# BMS_Master.net
KiCad netlist of a schematic drawn in EAGLE
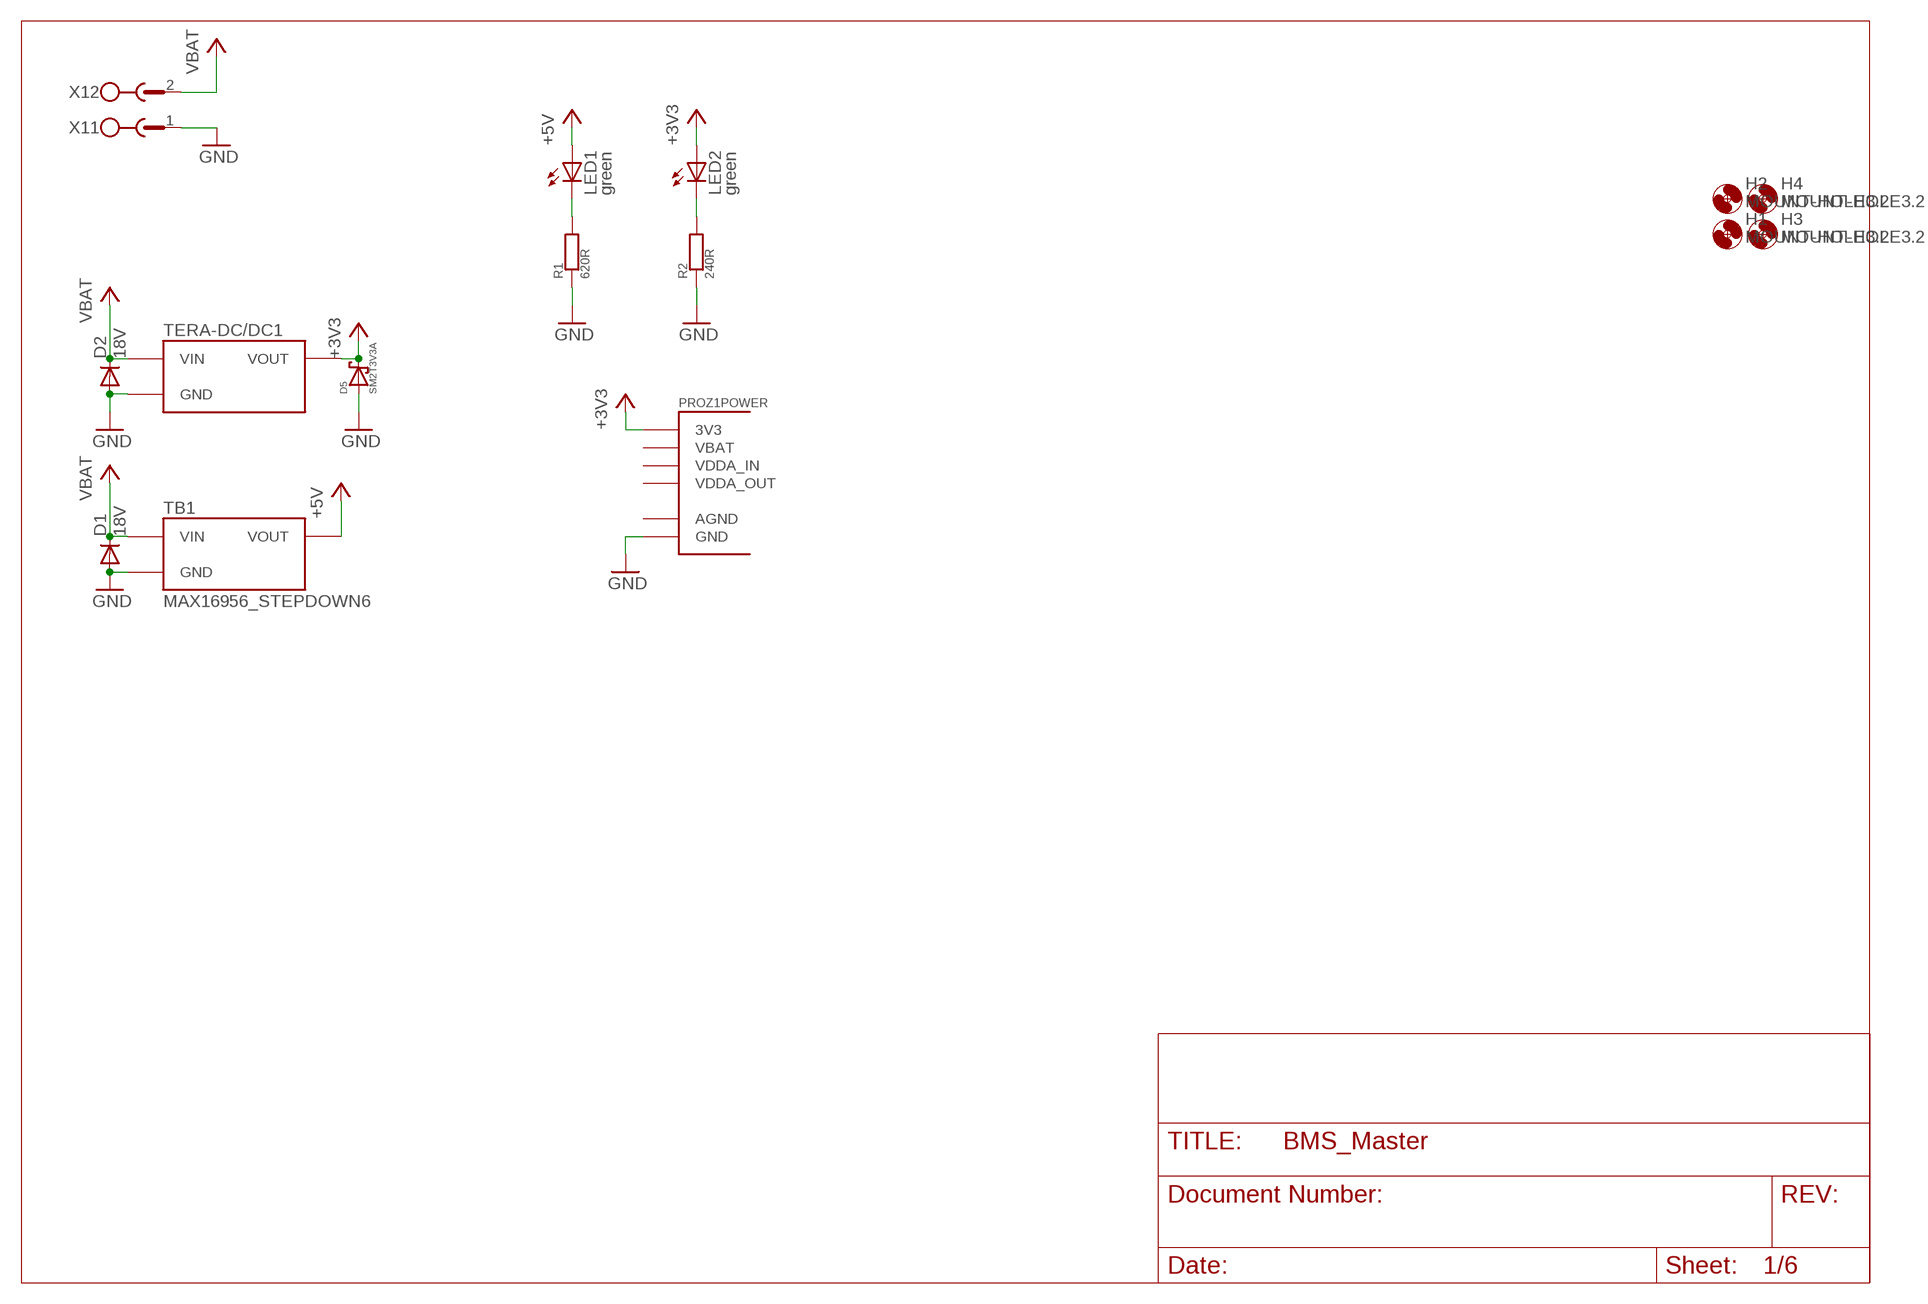
[diagram p0: schematic, sheet 1]
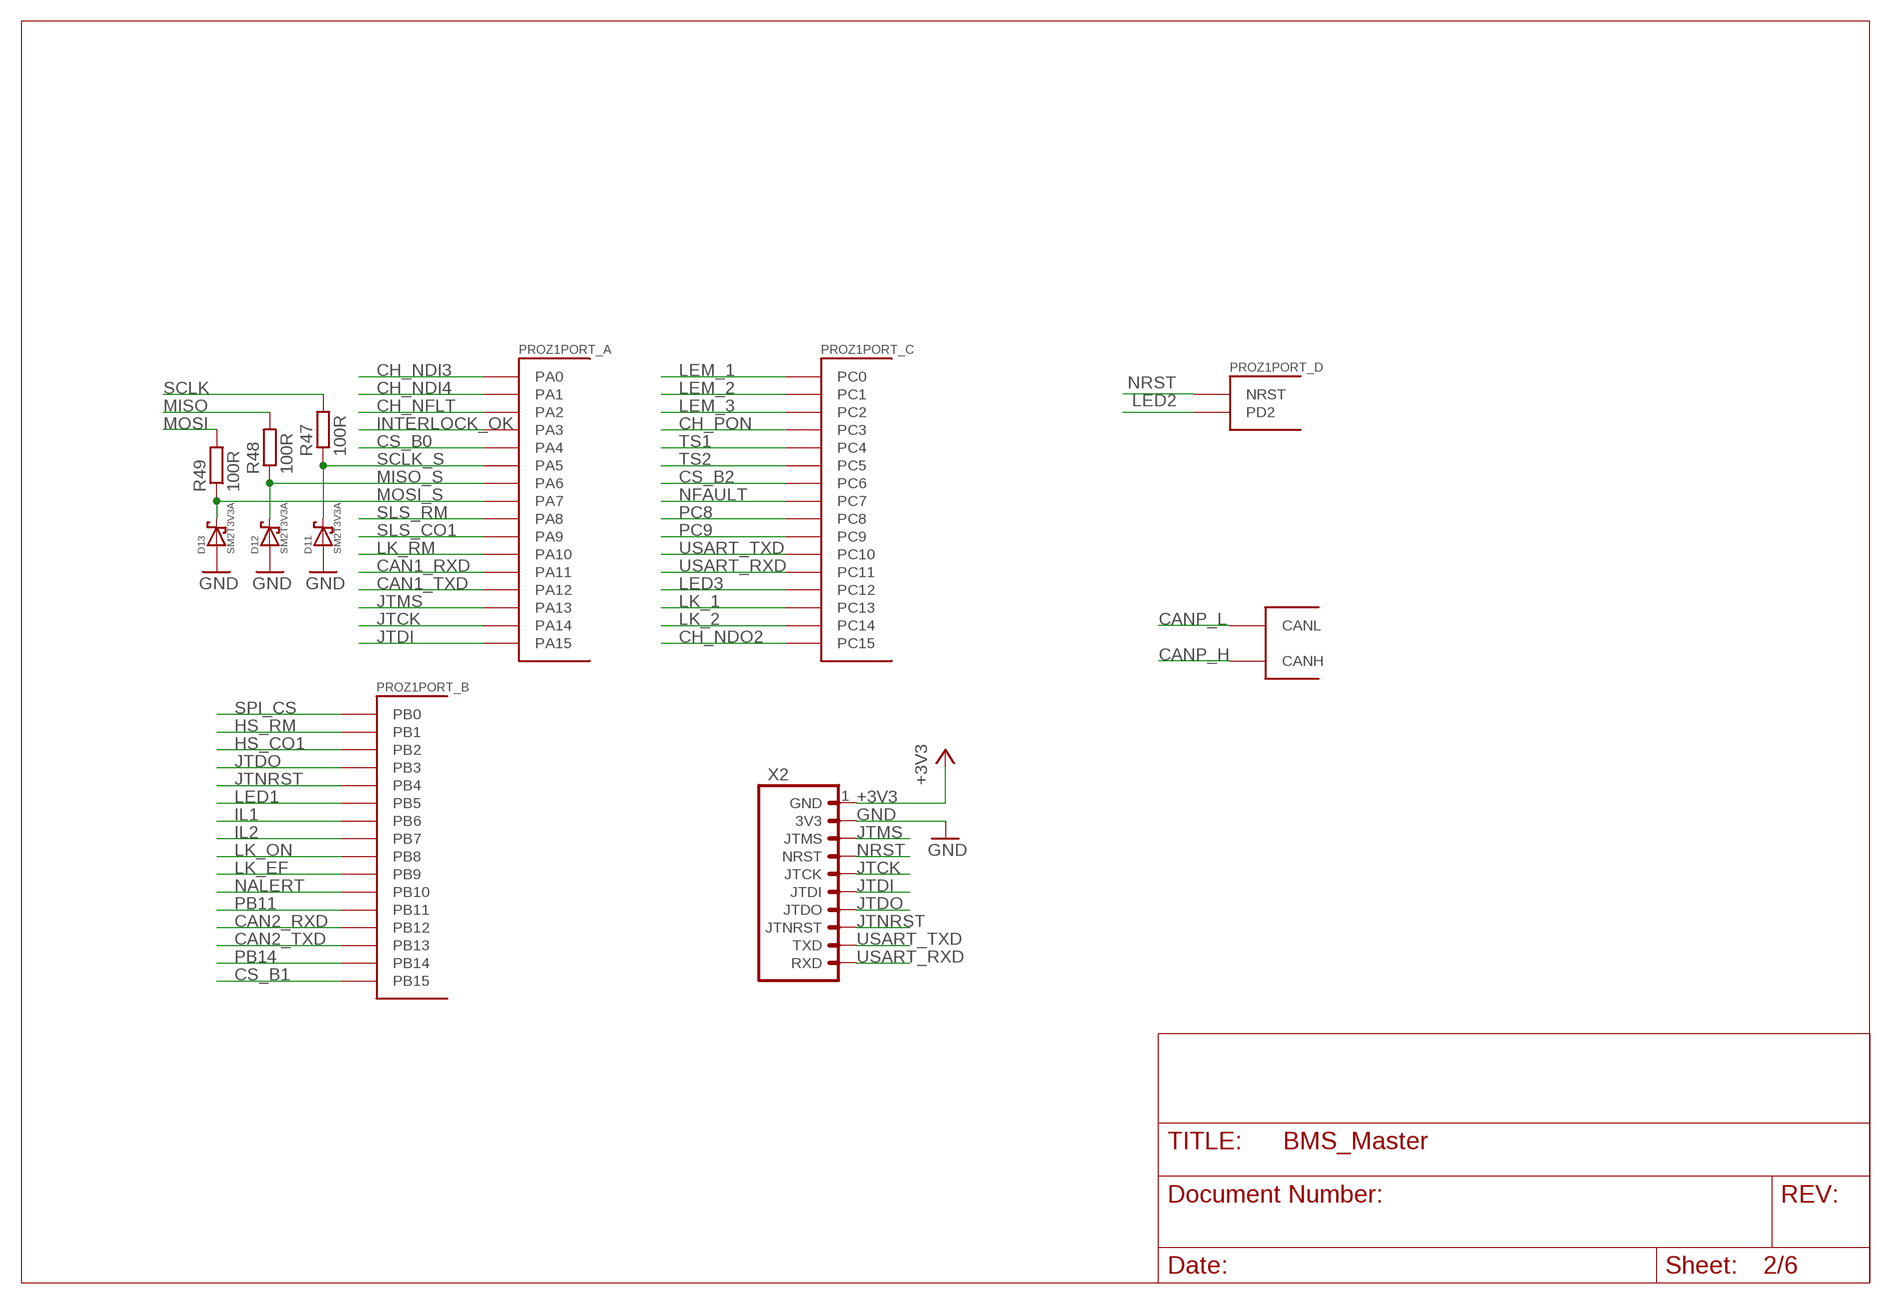
[diagram p1: schematic, sheet 2]
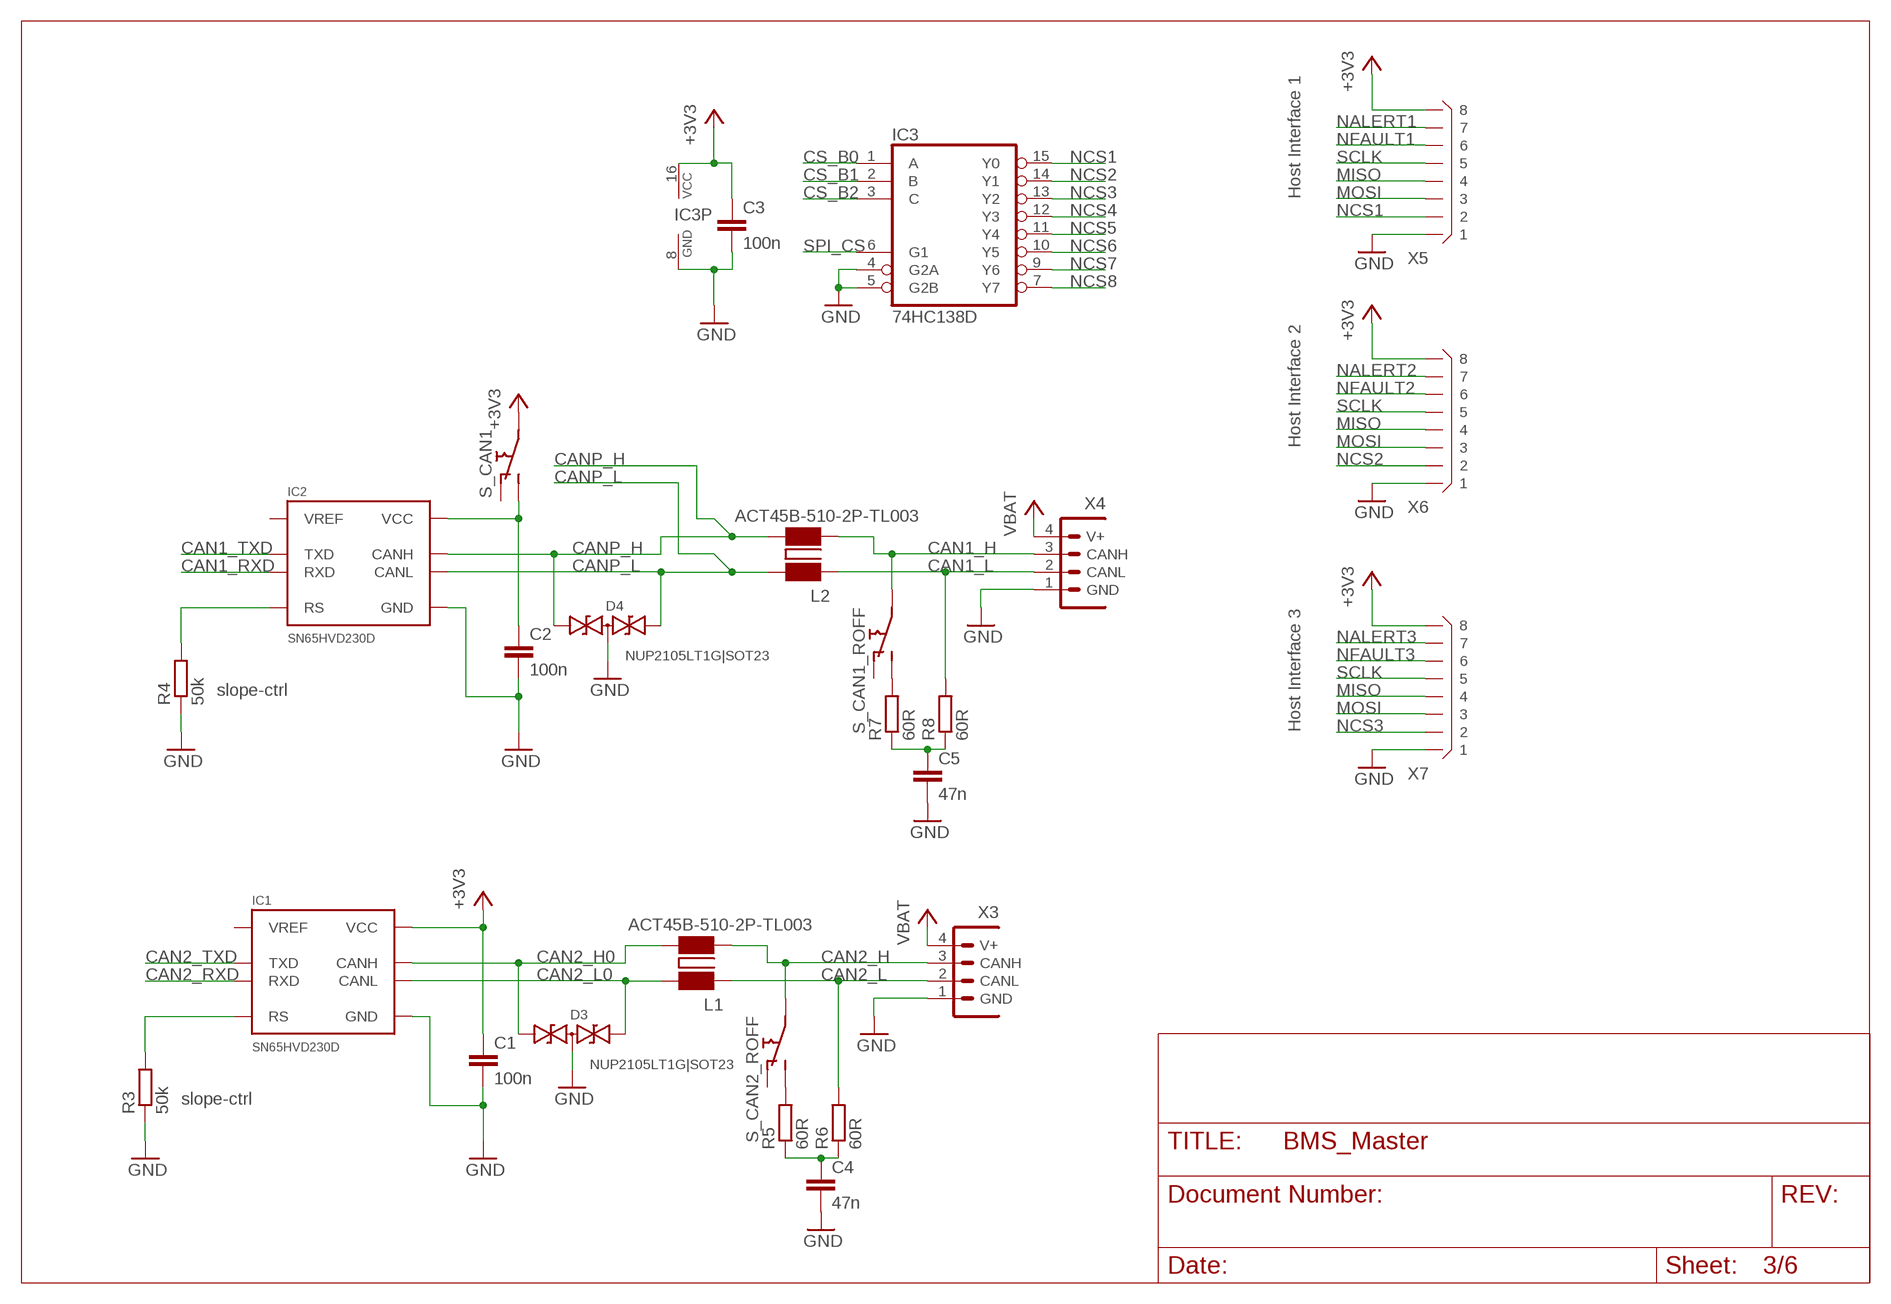
[diagram p2: schematic, sheet 3]
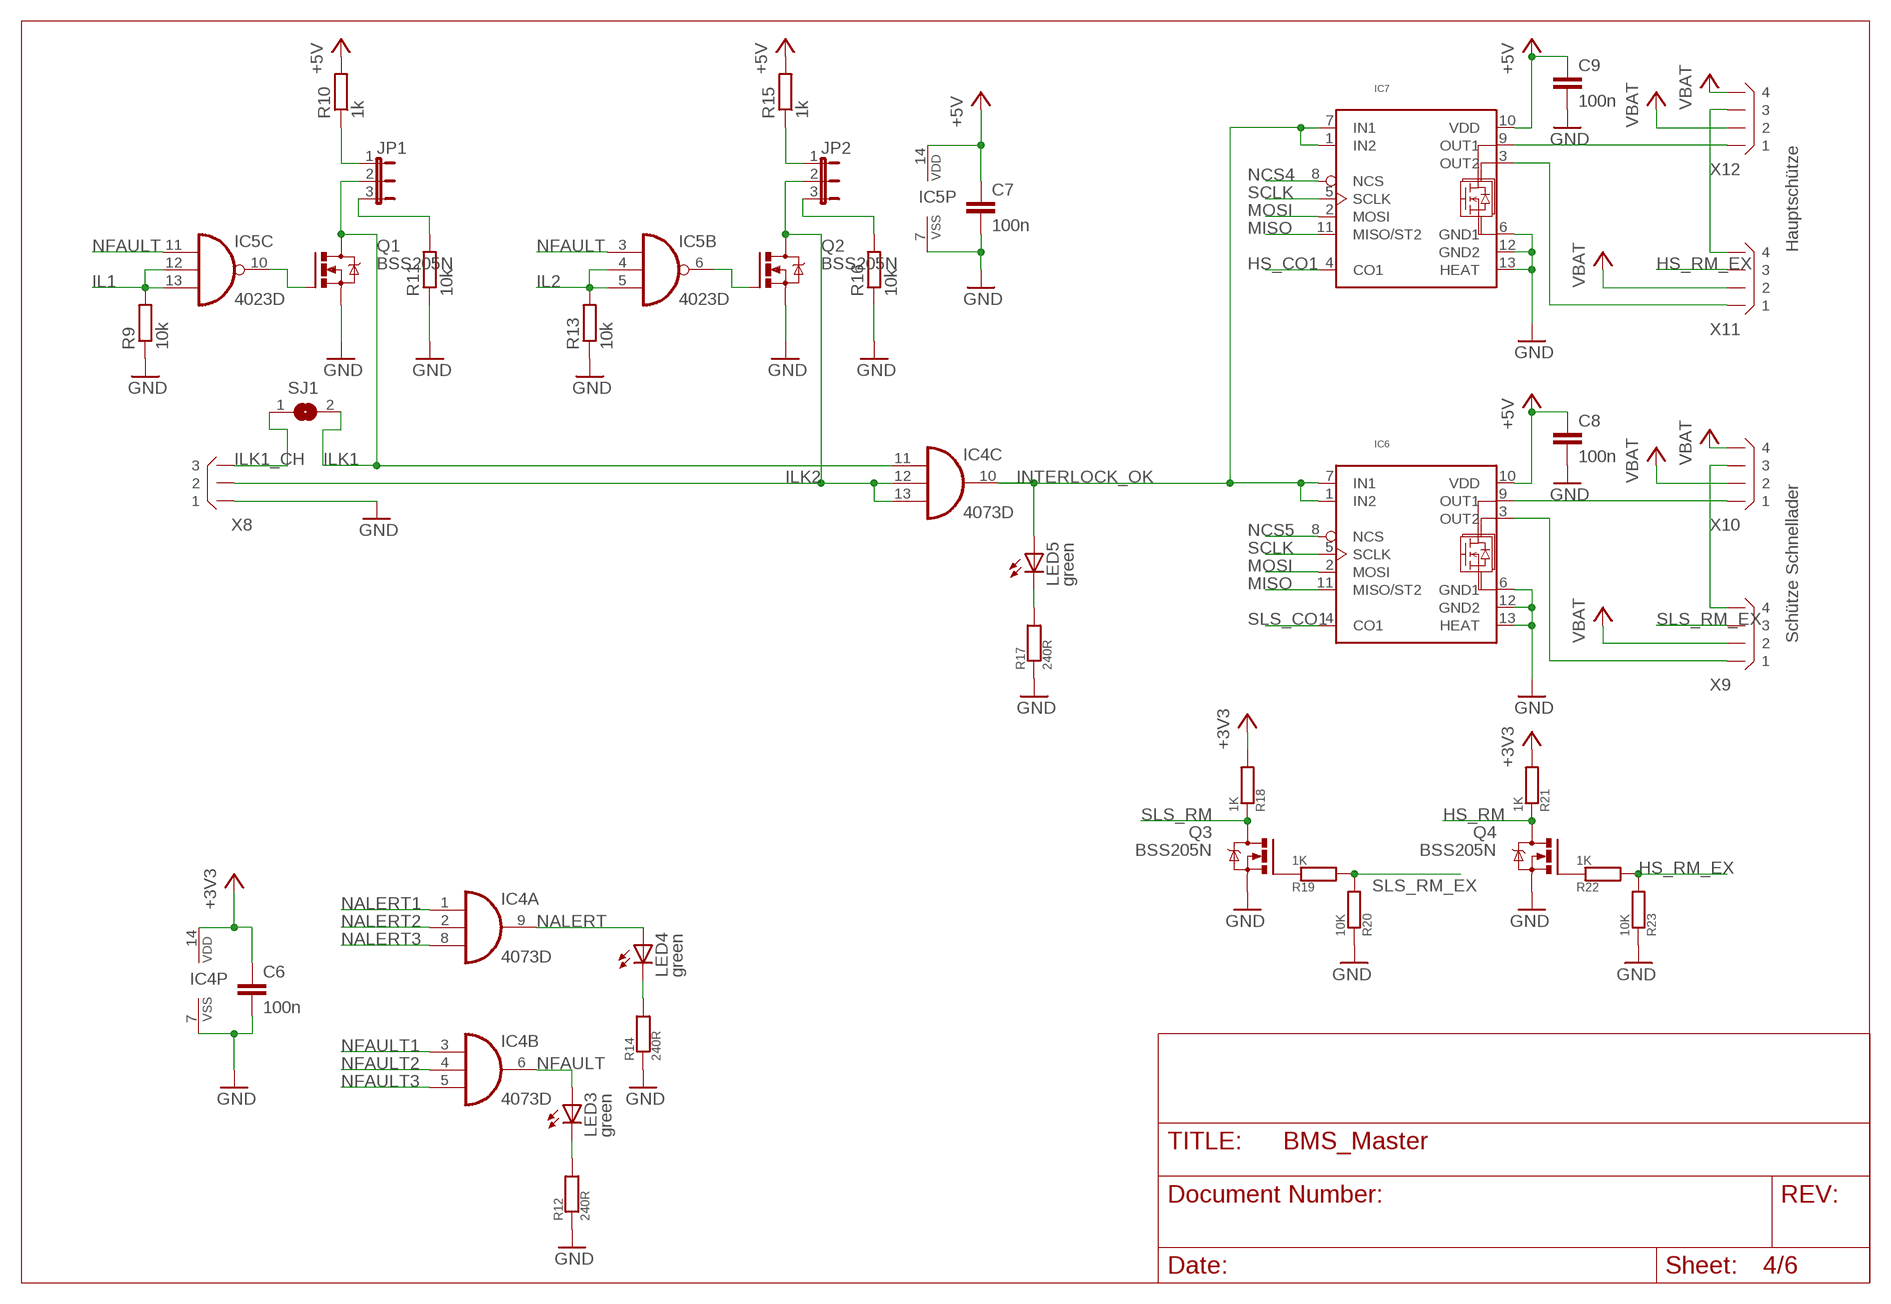
[diagram p3: schematic, sheet 4]
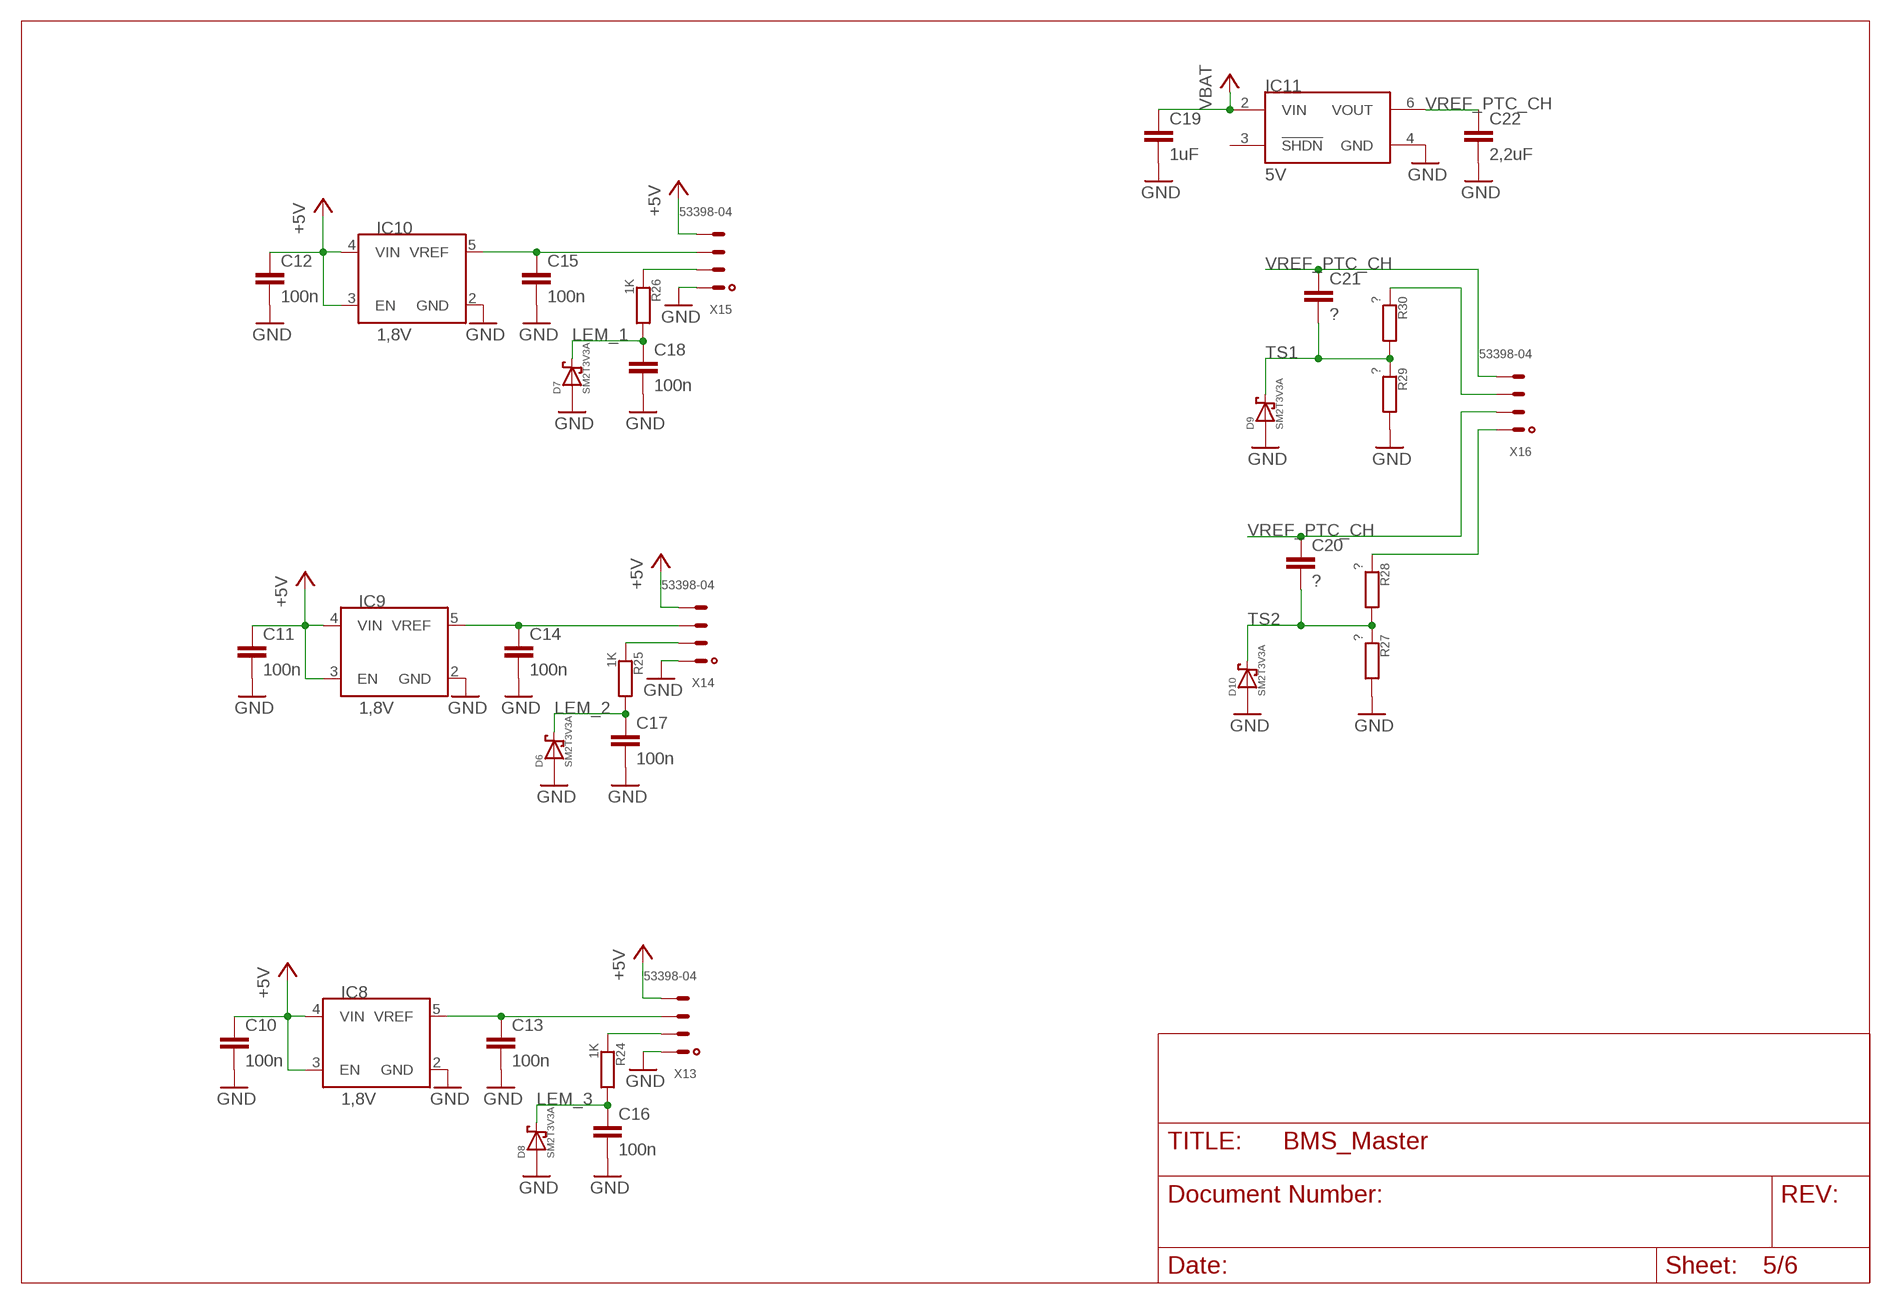
[diagram p4: schematic, sheet 5]
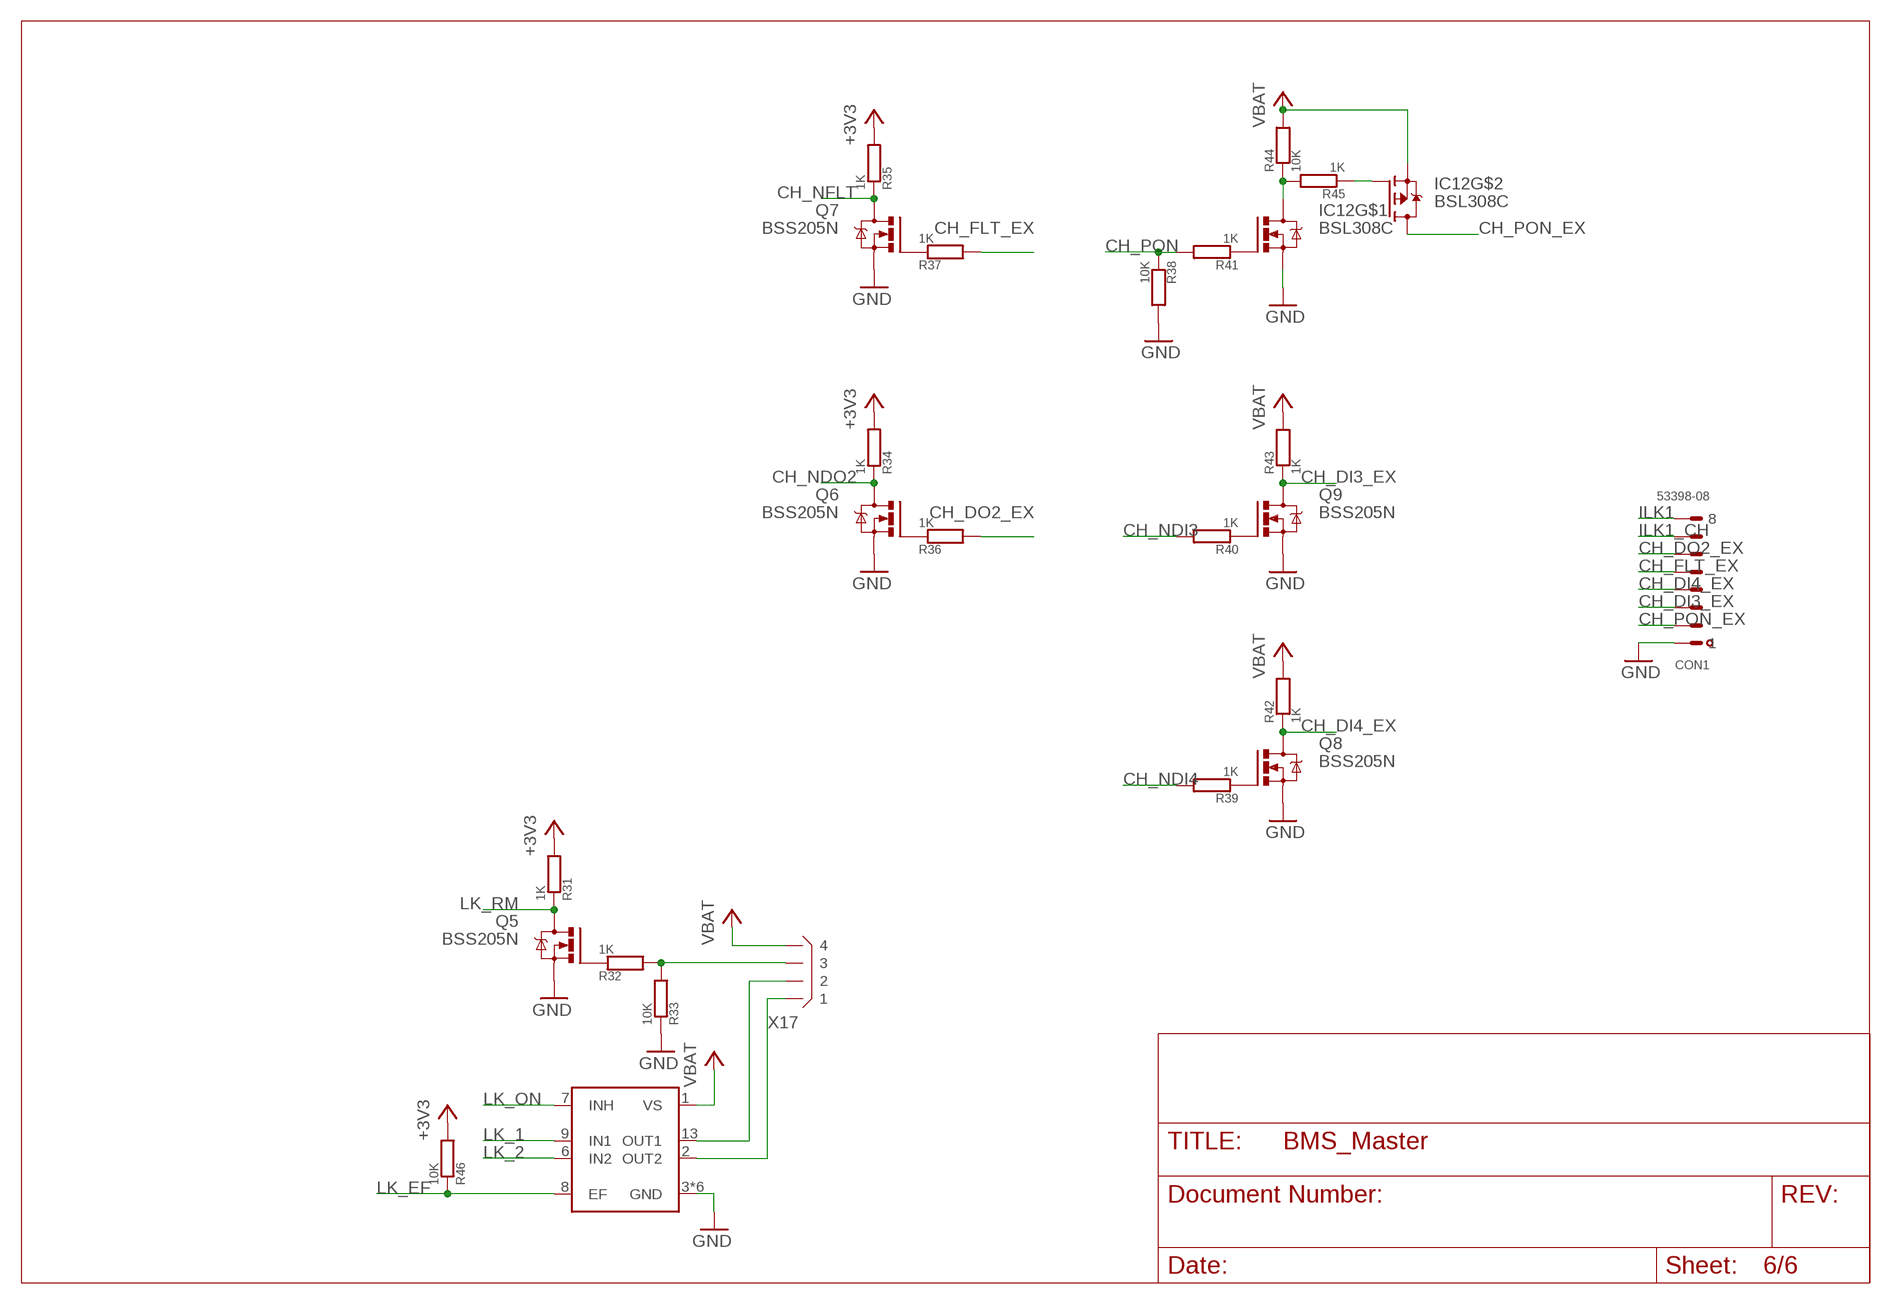
[diagram p5: schematic, sheet 6]

(export (version "E")
  (design (tool "Eeschema 10.0.6"))
  (components
    (comp (ref "C1")
      (value "100n")
      (footprint "eagle-import:C0805")
      (libsource (lib "eagle-import") (part "C-EUC0805"))
    )
    (comp (ref "C2")
      (value "100n")
      (footprint "eagle-import:C0805")
      (libsource (lib "eagle-import") (part "C-EUC0805"))
    )
    (comp (ref "C3")
      (value "100n")
      (footprint "eagle-import:C0805")
      (libsource (lib "eagle-import") (part "C-EUC0805"))
    )
    (comp (ref "C4")
      (value "47n")
      (footprint "eagle-import:C0805")
      (libsource (lib "eagle-import") (part "C-EUC0805"))
    )
    (comp (ref "C5")
      (value "47n")
      (footprint "eagle-import:C0805")
      (libsource (lib "eagle-import") (part "C-EUC0805"))
    )
    (comp (ref "D3")
      (value "NUP2105LT1G|SOT23")
      (footprint "eagle-import:SOT23")
      (libsource (lib "eagle-import") (part "NUP2105LT1G|SOT23"))
    )
    (comp (ref "D4")
      (value "NUP2105LT1G|SOT23")
      (footprint "eagle-import:SOT23")
      (libsource (lib "eagle-import") (part "NUP2105LT1G|SOT23"))
    )
    (comp (ref "IC1")
      (value "SN65HVD230D")
      (footprint "eagle-import:SO08")
      (libsource (lib "eagle-import") (part "SN65HVD23D0"))
    )
    (comp (ref "IC2")
      (value "SN65HVD230D")
      (footprint "eagle-import:SO08")
      (libsource (lib "eagle-import") (part "SN65HVD23D0"))
    )
    (comp (ref "IC3")
      (value "74HC138D")
      (footprint "eagle-import:SO16")
      (libsource (lib "eagle-import") (part "74138DHC"))
    )
    (comp (ref "L1")
      (value "ACT45B-510-2P-TL003")
      (footprint "eagle-import:ACT45B")
      (libsource (lib "eagle-import") (part "ACT45B-510-2P-TL003"))
    )
    (comp (ref "L2")
      (value "ACT45B-510-2P-TL003")
      (footprint "eagle-import:ACT45B")
      (libsource (lib "eagle-import") (part "ACT45B-510-2P-TL003"))
    )
    (comp (ref "R3")
      (value "50k")
      (footprint "eagle-import:R0805")
      (libsource (lib "eagle-import") (part "R-EU_R0805"))
    )
    (comp (ref "R4")
      (value "50k")
      (footprint "eagle-import:R0805")
      (libsource (lib "eagle-import") (part "R-EU_R0805"))
    )
    (comp (ref "R5")
      (value "60R")
      (footprint "eagle-import:R0805")
      (libsource (lib "eagle-import") (part "R-EU_R0805"))
    )
    (comp (ref "R6")
      (value "60R")
      (footprint "eagle-import:R0805")
      (libsource (lib "eagle-import") (part "R-EU_R0805"))
    )
    (comp (ref "R7")
      (value "60R")
      (footprint "eagle-import:R0805")
      (libsource (lib "eagle-import") (part "R-EU_R0805"))
    )
    (comp (ref "R8")
      (value "60R")
      (footprint "eagle-import:R0805")
      (libsource (lib "eagle-import") (part "R-EU_R0805"))
    )
    (comp (ref "S_CAN1")
      (value "JUMPER_ORS")
      (footprint "eagle-import:J_OR_S")
      (libsource (lib "eagle-import") (part "JUMPER_ORS"))
    )
    (comp (ref "S_CAN1_ROFF")
      (value "JUMPER_ORS")
      (footprint "eagle-import:J_OR_S")
      (libsource (lib "eagle-import") (part "JUMPER_ORS"))
    )
    (comp (ref "S_CAN2_ROFF")
      (value "JUMPER_ORS")
      (footprint "eagle-import:J_OR_S")
      (libsource (lib "eagle-import") (part "JUMPER_ORS"))
    )
    (comp (ref "X3")
      (value "CIOC_4-1-FV-A_CAN-BELEGUNG")
      (footprint "eagle-import:CIOC_4-1-FV")
      (libsource (lib "eagle-import") (part "CIOC_4-1-FV-A_CAN-BELEGUNG"))
    )
    (comp (ref "X4")
      (value "CIOC_4-1-FV-A_CAN-BELEGUNG")
      (footprint "eagle-import:CIOC_4-1-FV")
      (libsource (lib "eagle-import") (part "CIOC_4-1-FV-A_CAN-BELEGUNG"))
    )
    (comp (ref "X5")
      (value "B8B-XH")
      (footprint "eagle-import:B8B-XH")
      (libsource (lib "eagle-import") (part "?8B-XHB"))
    )
    (comp (ref "X6")
      (value "B8B-XH")
      (footprint "eagle-import:B8B-XH")
      (libsource (lib "eagle-import") (part "?8B-XHB"))
    )
    (comp (ref "X7")
      (value "B8B-XH")
      (footprint "eagle-import:B8B-XH")
      (libsource (lib "eagle-import") (part "?8B-XHB"))
    )
    (comp (ref "C10")
      (value "100n")
      (footprint "eagle-import:C0805")
      (libsource (lib "eagle-import") (part "C-EUC0805"))
    )
    (comp (ref "C11")
      (value "100n")
      (footprint "eagle-import:C0805")
      (libsource (lib "eagle-import") (part "C-EUC0805"))
    )
    (comp (ref "C12")
      (value "100n")
      (footprint "eagle-import:C0805")
      (libsource (lib "eagle-import") (part "C-EUC0805"))
    )
    (comp (ref "C13")
      (value "100n")
      (footprint "eagle-import:C0805")
      (libsource (lib "eagle-import") (part "C-EUC0805"))
    )
    (comp (ref "C14")
      (value "100n")
      (footprint "eagle-import:C0805")
      (libsource (lib "eagle-import") (part "C-EUC0805"))
    )
    (comp (ref "C15")
      (value "100n")
      (footprint "eagle-import:C0805")
      (libsource (lib "eagle-import") (part "C-EUC0805"))
    )
    (comp (ref "C16")
      (value "100n")
      (footprint "eagle-import:C0805")
      (libsource (lib "eagle-import") (part "C-EUC0805"))
    )
    (comp (ref "C17")
      (value "100n")
      (footprint "eagle-import:C0805")
      (libsource (lib "eagle-import") (part "C-EUC0805"))
    )
    (comp (ref "C18")
      (value "100n")
      (footprint "eagle-import:C0805")
      (libsource (lib "eagle-import") (part "C-EUC0805"))
    )
    (comp (ref "C19")
      (value "1uF")
      (footprint "eagle-import:C0805")
      (libsource (lib "eagle-import") (part "C-EUC0805"))
    )
    (comp (ref "C20")
      (value "?")
      (footprint "eagle-import:C0805")
      (libsource (lib "eagle-import") (part "C-EUC0805"))
    )
    (comp (ref "C21")
      (value "?")
      (footprint "eagle-import:C0805")
      (libsource (lib "eagle-import") (part "C-EUC0805"))
    )
    (comp (ref "C22")
      (value "2,2uF")
      (footprint "eagle-import:C0805")
      (libsource (lib "eagle-import") (part "C-EUC0805"))
    )
    (comp (ref "D6")
      (value "SM2T3V3A")
      (footprint "eagle-import:SM2T3V3A")
      (libsource (lib "eagle-import") (part "SM2T3V3A"))
    )
    (comp (ref "D7")
      (value "SM2T3V3A")
      (footprint "eagle-import:SM2T3V3A")
      (libsource (lib "eagle-import") (part "SM2T3V3A"))
    )
    (comp (ref "D8")
      (value "SM2T3V3A")
      (footprint "eagle-import:SM2T3V3A")
      (libsource (lib "eagle-import") (part "SM2T3V3A"))
    )
    (comp (ref "D9")
      (value "SM2T3V3A")
      (footprint "eagle-import:SM2T3V3A")
      (libsource (lib "eagle-import") (part "SM2T3V3A"))
    )
    (comp (ref "D10")
      (value "SM2T3V3A")
      (footprint "eagle-import:SM2T3V3A")
      (libsource (lib "eagle-import") (part "SM2T3V3A"))
    )
    (comp (ref "IC8")
      (value "1,8V")
      (footprint "eagle-import:SOT23-5L")
      (libsource (lib "eagle-import") (part "LM4132L"))
    )
    (comp (ref "IC9")
      (value "1,8V")
      (footprint "eagle-import:SOT23-5L")
      (libsource (lib "eagle-import") (part "LM4132L"))
    )
    (comp (ref "IC10")
      (value "1,8V")
      (footprint "eagle-import:SOT23-5L")
      (libsource (lib "eagle-import") (part "LM4132L"))
    )
    (comp (ref "IC11")
      (value "5V")
      (footprint "eagle-import:SO08")
      (libsource (lib "eagle-import") (part "LT1461"))
    )
    (comp (ref "R24")
      (value "1K")
      (footprint "eagle-import:R0805")
      (libsource (lib "eagle-import") (part "R"))
    )
    (comp (ref "R25")
      (value "1K")
      (footprint "eagle-import:R0805")
      (libsource (lib "eagle-import") (part "R"))
    )
    (comp (ref "R26")
      (value "1K")
      (footprint "eagle-import:R0805")
      (libsource (lib "eagle-import") (part "R"))
    )
    (comp (ref "R27")
      (value "?")
      (footprint "eagle-import:R0805")
      (libsource (lib "eagle-import") (part "R"))
    )
    (comp (ref "R28")
      (value "?")
      (footprint "eagle-import:R0805")
      (libsource (lib "eagle-import") (part "R"))
    )
    (comp (ref "R29")
      (value "?")
      (footprint "eagle-import:R0805")
      (libsource (lib "eagle-import") (part "R"))
    )
    (comp (ref "R30")
      (value "?")
      (footprint "eagle-import:R0805")
      (libsource (lib "eagle-import") (part "R"))
    )
    (comp (ref "X13")
      (value "53398-04")
      (footprint "eagle-import:53398-04")
      (libsource (lib "eagle-import") (part "53?-04398"))
    )
    (comp (ref "X14")
      (value "53398-04")
      (footprint "eagle-import:53398-04")
      (libsource (lib "eagle-import") (part "53?-04398"))
    )
    (comp (ref "X15")
      (value "53398-04")
      (footprint "eagle-import:53398-04")
      (libsource (lib "eagle-import") (part "53?-04398"))
    )
    (comp (ref "X16")
      (value "53398-04")
      (footprint "eagle-import:53398-04")
      (libsource (lib "eagle-import") (part "53?-04398"))
    )
    (comp (ref "D1")
      (value "18V")
      (footprint "eagle-import:DO214AA")
      (libsource (lib "eagle-import") (part "DIODE-DO214AA"))
    )
    (comp (ref "D2")
      (value "18V")
      (footprint "eagle-import:DO214AA")
      (libsource (lib "eagle-import") (part "DIODE-DO214AA"))
    )
    (comp (ref "D5")
      (value "SM2T3V3A")
      (footprint "eagle-import:SM2T3V3A")
      (libsource (lib "eagle-import") (part "SM2T3V3A"))
    )
    (comp (ref "H1")
      (value "MOUNT-HOLE3.2")
      (footprint "eagle-import:3,2")
      (libsource (lib "eagle-import") (part "MOUNT-HOLE3.2"))
    )
    (comp (ref "H2")
      (value "MOUNT-HOLE3.2")
      (footprint "eagle-import:3,2")
      (libsource (lib "eagle-import") (part "MOUNT-HOLE3.2"))
    )
    (comp (ref "H3")
      (value "MOUNT-HOLE3.2")
      (footprint "eagle-import:3,2")
      (libsource (lib "eagle-import") (part "MOUNT-HOLE3.2"))
    )
    (comp (ref "H4")
      (value "MOUNT-HOLE3.2")
      (footprint "eagle-import:3,2")
      (libsource (lib "eagle-import") (part "MOUNT-HOLE3.2"))
    )
    (comp (ref "LED1")
      (value "green")
      (footprint "eagle-import:CHIP-LED0805")
      (libsource (lib "eagle-import") (part "LEDCHIP-LED0805"))
    )
    (comp (ref "LED2")
      (value "green")
      (footprint "eagle-import:CHIP-LED0805")
      (libsource (lib "eagle-import") (part "LEDCHIP-LED0805"))
    )
    (comp (ref "PROZ1")
      (value "STM32F4_PROZESSORBOARDRPZ")
      (footprint "eagle-import:STM32F4_PROZESSORBOARD")
      (libsource (lib "eagle-import") (part "STM32F4_PROZESSORBOARDRPZ"))
    )
    (comp (ref "R1")
      (value "620R")
      (footprint "eagle-import:R0805")
      (libsource (lib "eagle-import") (part "R"))
    )
    (comp (ref "R2")
      (value "240R")
      (footprint "eagle-import:R0805")
      (libsource (lib "eagle-import") (part "R"))
    )
    (comp (ref "TB1")
      (value "MAX16956_STEPDOWN6")
      (footprint "eagle-import:MAX16956_STEPDOWN6")
      (libsource (lib "eagle-import") (part "MAX16956_STEPDOWN6"))
    )
    (comp (ref "TERA-DC/DC1")
      (value "MAX5035_STEPDOWN3")
      (footprint "eagle-import:MAX5035_STEPDOWN3")
      (libsource (lib "eagle-import") (part "MAX5035_STEPDOWN3"))
    )
    (comp (ref "X1")
      (value "MSTBX2MSTBV2_GF")
      (footprint "eagle-import:MSTBV2_GF")
      (libsource (lib "eagle-import") (part "MSTBX2MSTBV2_GF"))
    )
    (comp (ref "CON1")
      (value "53398-08")
      (footprint "eagle-import:53398-08")
      (libsource (lib "eagle-import") (part "53?-08398"))
    )
    (comp (ref "IC12")
      (value "BSL308C")
      (footprint "eagle-import:TSOP-6")
      (libsource (lib "eagle-import") (part "BSL308C"))
    )
    (comp (ref "IC13")
      (value "TLE4207GM")
      (footprint "eagle-import:INF-PG-DSO-14-22_M_1PRIMARY")
      (libsource (lib "eagle-import") (part "TLE4207GM"))
    )
    (comp (ref "Q5")
      (value "BSS205N")
      (footprint "eagle-import:SOT23")
      (libsource (lib "eagle-import") (part "BSS205N"))
    )
    (comp (ref "Q6")
      (value "BSS205N")
      (footprint "eagle-import:SOT23")
      (libsource (lib "eagle-import") (part "BSS205N"))
    )
    (comp (ref "Q7")
      (value "BSS205N")
      (footprint "eagle-import:SOT23")
      (libsource (lib "eagle-import") (part "BSS205N"))
    )
    (comp (ref "Q8")
      (value "BSS205N")
      (footprint "eagle-import:SOT23")
      (libsource (lib "eagle-import") (part "BSS205N"))
    )
    (comp (ref "Q9")
      (value "BSS205N")
      (footprint "eagle-import:SOT23")
      (libsource (lib "eagle-import") (part "BSS205N"))
    )
    (comp (ref "R31")
      (value "1K")
      (footprint "eagle-import:R0805")
      (libsource (lib "eagle-import") (part "R"))
    )
    (comp (ref "R32")
      (value "1K")
      (footprint "eagle-import:R0805")
      (libsource (lib "eagle-import") (part "R"))
    )
    (comp (ref "R33")
      (value "10K")
      (footprint "eagle-import:R0805")
      (libsource (lib "eagle-import") (part "R"))
    )
    (comp (ref "R34")
      (value "1K")
      (footprint "eagle-import:R0805")
      (libsource (lib "eagle-import") (part "R"))
    )
    (comp (ref "R35")
      (value "1K")
      (footprint "eagle-import:R0805")
      (libsource (lib "eagle-import") (part "R"))
    )
    (comp (ref "R36")
      (value "1K")
      (footprint "eagle-import:R0805")
      (libsource (lib "eagle-import") (part "R"))
    )
    (comp (ref "R37")
      (value "1K")
      (footprint "eagle-import:R0805")
      (libsource (lib "eagle-import") (part "R"))
    )
    (comp (ref "R38")
      (value "10K")
      (footprint "eagle-import:R0805")
      (libsource (lib "eagle-import") (part "R"))
    )
    (comp (ref "R39")
      (value "1K")
      (footprint "eagle-import:R0805")
      (libsource (lib "eagle-import") (part "R"))
    )
    (comp (ref "R40")
      (value "1K")
      (footprint "eagle-import:R0805")
      (libsource (lib "eagle-import") (part "R"))
    )
    (comp (ref "R41")
      (value "1K")
      (footprint "eagle-import:R0805")
      (libsource (lib "eagle-import") (part "R"))
    )
    (comp (ref "R42")
      (value "1K")
      (footprint "eagle-import:R0805")
      (libsource (lib "eagle-import") (part "R"))
    )
    (comp (ref "R43")
      (value "1K")
      (footprint "eagle-import:R0805")
      (libsource (lib "eagle-import") (part "R"))
    )
    (comp (ref "R44")
      (value "10K")
      (footprint "eagle-import:R0805")
      (libsource (lib "eagle-import") (part "R"))
    )
    (comp (ref "R45")
      (value "1K")
      (footprint "eagle-import:R0805")
      (libsource (lib "eagle-import") (part "R"))
    )
    (comp (ref "R46")
      (value "10K")
      (footprint "eagle-import:R0805")
      (libsource (lib "eagle-import") (part "R"))
    )
    (comp (ref "X17")
      (value "B4B-XH")
      (footprint "eagle-import:B4B-XH")
      (libsource (lib "eagle-import") (part "?4B-XHB"))
    )
    (comp (ref "C6")
      (value "100n")
      (footprint "eagle-import:C0805")
      (libsource (lib "eagle-import") (part "C-EUC0805"))
    )
    (comp (ref "C7")
      (value "100n")
      (footprint "eagle-import:C0805")
      (libsource (lib "eagle-import") (part "C-EUC0805"))
    )
    (comp (ref "C8")
      (value "100n")
      (footprint "eagle-import:C0805")
      (libsource (lib "eagle-import") (part "C-EUC0805"))
    )
    (comp (ref "C9")
      (value "100n")
      (footprint "eagle-import:C0805")
      (libsource (lib "eagle-import") (part "C-EUC0805"))
    )
    (comp (ref "IC4")
      (value "4073D")
      (footprint "eagle-import:SO14")
      (libsource (lib "eagle-import") (part "4073D"))
    )
    (comp (ref "IC5")
      (value "4023D")
      (footprint "eagle-import:SO14")
      (libsource (lib "eagle-import") (part "4023D"))
    )
    (comp (ref "IC6")
      (value "TLE8102SGN")
      (footprint "eagle-import:INF-PG-DSO-12-11_N_1PRIMARY")
      (libsource (lib "eagle-import") (part "TLE8102SGN"))
    )
    (comp (ref "IC7")
      (value "TLE8102SGN")
      (footprint "eagle-import:INF-PG-DSO-12-11_N_1PRIMARY")
      (libsource (lib "eagle-import") (part "TLE8102SGN"))
    )
    (comp (ref "JP1")
      (value "JP2E")
      (footprint "eagle-import:JP2")
      (libsource (lib "eagle-import") (part "JP2E"))
    )
    (comp (ref "JP2")
      (value "JP2E")
      (footprint "eagle-import:JP2")
      (libsource (lib "eagle-import") (part "JP2E"))
    )
    (comp (ref "LED3")
      (value "green")
      (footprint "eagle-import:CHIPLED_0805")
      (libsource (lib "eagle-import") (part "LEDCHIPLED_0805"))
    )
    (comp (ref "LED4")
      (value "green")
      (footprint "eagle-import:CHIPLED_0805")
      (libsource (lib "eagle-import") (part "LEDCHIPLED_0805"))
    )
    (comp (ref "LED5")
      (value "green")
      (footprint "eagle-import:CHIPLED_0805")
      (libsource (lib "eagle-import") (part "LEDCHIPLED_0805"))
    )
    (comp (ref "Q1")
      (value "BSS205N")
      (footprint "eagle-import:SOT23")
      (libsource (lib "eagle-import") (part "BSS205N"))
    )
    (comp (ref "Q2")
      (value "BSS205N")
      (footprint "eagle-import:SOT23")
      (libsource (lib "eagle-import") (part "BSS205N"))
    )
    (comp (ref "Q3")
      (value "BSS205N")
      (footprint "eagle-import:SOT23")
      (libsource (lib "eagle-import") (part "BSS205N"))
    )
    (comp (ref "Q4")
      (value "BSS205N")
      (footprint "eagle-import:SOT23")
      (libsource (lib "eagle-import") (part "BSS205N"))
    )
    (comp (ref "R9")
      (value "10k")
      (footprint "eagle-import:R0805")
      (libsource (lib "eagle-import") (part "R-EU_R0805"))
    )
    (comp (ref "R10")
      (value "1k")
      (footprint "eagle-import:R0805")
      (libsource (lib "eagle-import") (part "R-EU_R0805"))
    )
    (comp (ref "R11")
      (value "10k")
      (footprint "eagle-import:R0805")
      (libsource (lib "eagle-import") (part "R-EU_R0805"))
    )
    (comp (ref "R12")
      (value "240R")
      (footprint "eagle-import:R0805")
      (libsource (lib "eagle-import") (part "R"))
    )
    (comp (ref "R13")
      (value "10k")
      (footprint "eagle-import:R0805")
      (libsource (lib "eagle-import") (part "R-EU_R0805"))
    )
    (comp (ref "R14")
      (value "240R")
      (footprint "eagle-import:R0805")
      (libsource (lib "eagle-import") (part "R"))
    )
    (comp (ref "R15")
      (value "1k")
      (footprint "eagle-import:R0805")
      (libsource (lib "eagle-import") (part "R-EU_R0805"))
    )
    (comp (ref "R16")
      (value "10k")
      (footprint "eagle-import:R0805")
      (libsource (lib "eagle-import") (part "R-EU_R0805"))
    )
    (comp (ref "R17")
      (value "240R")
      (footprint "eagle-import:R0805")
      (libsource (lib "eagle-import") (part "R"))
    )
    (comp (ref "R18")
      (value "1K")
      (footprint "eagle-import:R0805")
      (libsource (lib "eagle-import") (part "R"))
    )
    (comp (ref "R19")
      (value "1K")
      (footprint "eagle-import:R0805")
      (libsource (lib "eagle-import") (part "R"))
    )
    (comp (ref "R20")
      (value "10K")
      (footprint "eagle-import:R0805")
      (libsource (lib "eagle-import") (part "R"))
    )
    (comp (ref "R21")
      (value "1K")
      (footprint "eagle-import:R0805")
      (libsource (lib "eagle-import") (part "R"))
    )
    (comp (ref "R22")
      (value "1K")
      (footprint "eagle-import:R0805")
      (libsource (lib "eagle-import") (part "R"))
    )
    (comp (ref "R23")
      (value "10K")
      (footprint "eagle-import:R0805")
      (libsource (lib "eagle-import") (part "R"))
    )
    (comp (ref "SJ1") (value "SJ") (footprint "eagle-import:SJ") (libsource (lib "eagle-import") (part "SJ")))
    (comp (ref "X8")
      (value "B3B-XH")
      (footprint "eagle-import:B3B-XH")
      (libsource (lib "eagle-import") (part "?3B-XHB"))
    )
    (comp (ref "X9")
      (value "B4B-XH")
      (footprint "eagle-import:B4B-XH")
      (libsource (lib "eagle-import") (part "?4B-XHB"))
    )
    (comp (ref "X10")
      (value "B4B-XH")
      (footprint "eagle-import:B4B-XH")
      (libsource (lib "eagle-import") (part "?4B-XHB"))
    )
    (comp (ref "X11")
      (value "B4B-XH")
      (footprint "eagle-import:B4B-XH")
      (libsource (lib "eagle-import") (part "?4B-XHB"))
    )
    (comp (ref "X12")
      (value "B4B-XH")
      (footprint "eagle-import:B4B-XH")
      (libsource (lib "eagle-import") (part "?4B-XHB"))
    )
    (comp (ref "D11")
      (value "SM2T3V3A")
      (footprint "eagle-import:SM2T3V3A")
      (libsource (lib "eagle-import") (part "SM2T3V3A"))
    )
    (comp (ref "D12")
      (value "SM2T3V3A")
      (footprint "eagle-import:SM2T3V3A")
      (libsource (lib "eagle-import") (part "SM2T3V3A"))
    )
    (comp (ref "D13")
      (value "SM2T3V3A")
      (footprint "eagle-import:SM2T3V3A")
      (libsource (lib "eagle-import") (part "SM2T3V3A"))
    )
    (comp (ref "R47")
      (value "100R")
      (footprint "eagle-import:R0805")
      (libsource (lib "eagle-import") (part "R-EU_R0805"))
    )
    (comp (ref "R48")
      (value "100R")
      (footprint "eagle-import:R0805")
      (libsource (lib "eagle-import") (part "R-EU_R0805"))
    )
    (comp (ref "R49")
      (value "100R")
      (footprint "eagle-import:R0805")
      (libsource (lib "eagle-import") (part "R-EU_R0805"))
    )
    (comp (ref "X2")
      (value "TERA-PROG-DEBUG-10GERADE")
      (footprint "eagle-import:90130-1110")
      (libsource (lib "eagle-import") (part "TERA-PROG-DEBUG-10GERADE"))
    )
  )
  (nets
    (net (code "1") (name "+3V3") (class "Default")
      (node (ref "C1") (pin "1") (pinfunction "1_1") (pintype "passive"))
      (node (ref "C3") (pin "1") (pinfunction "1_1") (pintype "passive"))
      (node (ref "C6") (pin "1") (pinfunction "1_1") (pintype "passive"))
      (node (ref "D5") (pin "P$2") (pinfunction "P$2_P$2") (pintype "bidirectional"))
      (node (ref "IC1") (pin "3") (pinfunction "VCC_3") (pintype "power_in"))
      (node (ref "IC3") (pin "16") (pinfunction "VCC_16") (pintype "power_in"))
      (node (ref "IC4") (pin "14") (pinfunction "VDD_14") (pintype "power_in"))
      (node (ref "LED2") (pin "A") (pinfunction "A_A") (pintype "passive"))
      (node (ref "PROZ1") (pin "45") (pinfunction "3V3_45") (pintype "passive"))
      (node (ref "PROZ1") (pin "46") (pinfunction "3V3_46") (pintype "passive"))
      (node (ref "R18") (pin "2") (pinfunction "2_2") (pintype "passive"))
      (node (ref "R21") (pin "2") (pinfunction "2_2") (pintype "passive"))
      (node (ref "R31") (pin "2") (pinfunction "2_2") (pintype "passive"))
      (node (ref "R34") (pin "2") (pinfunction "2_2") (pintype "passive"))
      (node (ref "R35") (pin "2") (pinfunction "2_2") (pintype "passive"))
      (node (ref "R46") (pin "2") (pinfunction "2_2") (pintype "passive"))
      (node (ref "S_CAN1") (pin "P$1") (pinfunction "P$1_P$1") (pintype "bidirectional"))
      (node (ref "TERA-DC/DC1") (pin "VOUT") (pinfunction "VOUT_VOUT") (pintype "passive"))
      (node (ref "X2") (pin "1") (pinfunction "GND_1") (pintype "passive"))
      (node (ref "X5") (pin "P$8") (pinfunction "8_P$8") (pintype "bidirectional"))
      (node (ref "X6") (pin "P$8") (pinfunction "8_P$8") (pintype "bidirectional"))
      (node (ref "X7") (pin "P$8") (pinfunction "8_P$8") (pintype "bidirectional"))
    )
    (net (code "2") (name "+5V") (class "Default")
      (node (ref "C10") (pin "1") (pinfunction "1_1") (pintype "passive"))
      (node (ref "C11") (pin "1") (pinfunction "1_1") (pintype "passive"))
      (node (ref "C12") (pin "1") (pinfunction "1_1") (pintype "passive"))
      (node (ref "C7") (pin "1") (pinfunction "1_1") (pintype "passive"))
      (node (ref "C8") (pin "1") (pinfunction "1_1") (pintype "passive"))
      (node (ref "C9") (pin "1") (pinfunction "1_1") (pintype "passive"))
      (node (ref "IC10") (pin "3") (pinfunction "EN_3") (pintype "bidirectional"))
      (node (ref "IC10") (pin "4") (pinfunction "VIN_4") (pintype "bidirectional"))
      (node (ref "IC5") (pin "14") (pinfunction "VDD_14") (pintype "power_in"))
      (node (ref "IC6") (pin "10") (pinfunction "VDD_10") (pintype "bidirectional"))
      (node (ref "IC7") (pin "10") (pinfunction "VDD_10") (pintype "bidirectional"))
      (node (ref "IC8") (pin "3") (pinfunction "EN_3") (pintype "bidirectional"))
      (node (ref "IC8") (pin "4") (pinfunction "VIN_4") (pintype "bidirectional"))
      (node (ref "IC9") (pin "3") (pinfunction "EN_3") (pintype "bidirectional"))
      (node (ref "IC9") (pin "4") (pinfunction "VIN_4") (pintype "bidirectional"))
      (node (ref "LED1") (pin "A") (pinfunction "A_A") (pintype "passive"))
      (node (ref "R10") (pin "2") (pinfunction "2_2") (pintype "passive"))
      (node (ref "R15") (pin "2") (pinfunction "2_2") (pintype "passive"))
      (node (ref "TB1") (pin "VOUT") (pinfunction "VOUT_VOUT") (pintype "passive"))
      (node (ref "X13") (pin "4") (pinfunction "4_4") (pintype "passive"))
      (node (ref "X14") (pin "4") (pinfunction "4_4") (pintype "passive"))
      (node (ref "X15") (pin "4") (pinfunction "4_4") (pintype "passive"))
    )
    (net (code "3") (name "CAN1_H") (class "Default")
      (node (ref "L2") (pin "P$1") (pinfunction "1_P$1") (pintype "passive"))
      (node (ref "S_CAN1_ROFF") (pin "P$1") (pinfunction "P$1_P$1") (pintype "bidirectional"))
      (node (ref "X4") (pin "3") (pinfunction "CANH_3") (pintype "passive"))
    )
    (net (code "4") (name "CAN1_L") (class "Default")
      (node (ref "L2") (pin "P$3") (pinfunction "3_P$3") (pintype "passive"))
      (node (ref "R8") (pin "2") (pinfunction "2_2") (pintype "passive"))
      (node (ref "X4") (pin "2") (pinfunction "CANL_2") (pintype "passive"))
    )
    (net (code "5") (name "CAN1_RXD") (class "Default")
      (node (ref "IC2") (pin "4") (pinfunction "RXD_4") (pintype "output"))
      (node (ref "PROZ1") (pin "26") (pinfunction "PA11_26") (pintype "bidirectional"))
    )
    (net (code "6") (name "CAN1_TXD") (class "Default")
      (node (ref "IC2") (pin "1") (pinfunction "TXD_1") (pintype "input"))
      (node (ref "PROZ1") (pin "24") (pinfunction "PA12_24") (pintype "bidirectional"))
    )
    (net (code "7") (name "CAN2_H") (class "Default")
      (node (ref "L1") (pin "P$1") (pinfunction "1_P$1") (pintype "passive"))
      (node (ref "S_CAN2_ROFF") (pin "P$1") (pinfunction "P$1_P$1") (pintype "bidirectional"))
      (node (ref "X3") (pin "3") (pinfunction "CANH_3") (pintype "passive"))
    )
    (net (code "8") (name "CAN2_H0") (class "Default")
      (node (ref "D3") (pin "1") (pinfunction "P$1_1") (pintype "passive"))
      (node (ref "IC1") (pin "7") (pinfunction "CANH_7") (pintype "bidirectional"))
      (node (ref "L1") (pin "P$2") (pinfunction "2_P$2") (pintype "passive"))
    )
    (net (code "9") (name "CAN2_L") (class "Default")
      (node (ref "L1") (pin "P$3") (pinfunction "3_P$3") (pintype "passive"))
      (node (ref "R6") (pin "2") (pinfunction "2_2") (pintype "passive"))
      (node (ref "X3") (pin "2") (pinfunction "CANL_2") (pintype "passive"))
    )
    (net (code "10") (name "CAN2_L0") (class "Default")
      (node (ref "D3") (pin "2") (pinfunction "P$2_2") (pintype "passive"))
      (node (ref "IC1") (pin "6") (pinfunction "CANL_6") (pintype "bidirectional"))
      (node (ref "L1") (pin "P$4") (pinfunction "4_P$4") (pintype "passive"))
    )
    (net (code "11") (name "CAN2_RXD") (class "Default")
      (node (ref "IC1") (pin "4") (pinfunction "RXD_4") (pintype "output"))
      (node (ref "PROZ1") (pin "50") (pinfunction "PB12_50") (pintype "bidirectional"))
    )
    (net (code "12") (name "CAN2_TXD") (class "Default")
      (node (ref "IC1") (pin "1") (pinfunction "TXD_1") (pintype "input"))
      (node (ref "PROZ1") (pin "49") (pinfunction "PB13_49") (pintype "bidirectional"))
    )
    (net (code "13") (name "CANP_H") (class "Default")
      (node (ref "D4") (pin "1") (pinfunction "P$1_1") (pintype "passive"))
      (node (ref "IC2") (pin "7") (pinfunction "CANH_7") (pintype "bidirectional"))
      (node (ref "L2") (pin "P$2") (pinfunction "2_P$2") (pintype "passive"))
      (node (ref "PROZ1") (pin "31") (pinfunction "CANH_31") (pintype "bidirectional"))
    )
    (net (code "14") (name "CANP_L") (class "Default")
      (node (ref "D4") (pin "2") (pinfunction "P$2_2") (pintype "passive"))
      (node (ref "IC2") (pin "6") (pinfunction "CANL_6") (pintype "bidirectional"))
      (node (ref "L2") (pin "P$4") (pinfunction "4_P$4") (pintype "passive"))
      (node (ref "PROZ1") (pin "32") (pinfunction "CANL_32") (pintype "bidirectional"))
    )
    (net (code "15") (name "CH_DI3_EX") (class "Default")
      (node (ref "CON1") (pin "3") (pinfunction "3_3") (pintype "passive"))
      (node (ref "Q9") (pin "3") (pinfunction "D_3") (pintype "passive"))
      (node (ref "R43") (pin "1") (pinfunction "1_1") (pintype "passive"))
    )
    (net (code "16") (name "CH_DI4_EX") (class "Default")
      (node (ref "CON1") (pin "4") (pinfunction "4_4") (pintype "passive"))
      (node (ref "Q8") (pin "3") (pinfunction "D_3") (pintype "passive"))
      (node (ref "R42") (pin "1") (pinfunction "1_1") (pintype "passive"))
    )
    (net (code "17") (name "CH_DO2_EX") (class "Default")
      (node (ref "CON1") (pin "6") (pinfunction "6_6") (pintype "passive"))
      (node (ref "R36") (pin "2") (pinfunction "2_2") (pintype "passive"))
    )
    (net (code "18") (name "CH_FLT_EX") (class "Default")
      (node (ref "CON1") (pin "5") (pinfunction "5_5") (pintype "passive"))
      (node (ref "R37") (pin "2") (pinfunction "2_2") (pintype "passive"))
    )
    (net (code "19") (name "CH_NDI3") (class "Default")
      (node (ref "PROZ1") (pin "7") (pinfunction "PA0_7") (pintype "bidirectional"))
      (node (ref "R40") (pin "2") (pinfunction "2_2") (pintype "passive"))
    )
    (net (code "20") (name "CH_NDI4") (class "Default")
      (node (ref "PROZ1") (pin "5") (pinfunction "PA1_5") (pintype "bidirectional"))
      (node (ref "R39") (pin "2") (pinfunction "2_2") (pintype "passive"))
    )
    (net (code "21") (name "CH_NDO2") (class "Default")
      (node (ref "PROZ1") (pin "19") (pinfunction "PC15_19") (pintype "bidirectional"))
      (node (ref "Q6") (pin "3") (pinfunction "D_3") (pintype "passive"))
      (node (ref "R34") (pin "1") (pinfunction "1_1") (pintype "passive"))
    )
    (net (code "22") (name "CH_NFLT") (class "Default")
      (node (ref "PROZ1") (pin "3") (pinfunction "PA2_3") (pintype "bidirectional"))
      (node (ref "Q7") (pin "3") (pinfunction "D_3") (pintype "passive"))
      (node (ref "R35") (pin "1") (pinfunction "1_1") (pintype "passive"))
    )
    (net (code "23") (name "CH_PON") (class "Default")
      (node (ref "PROZ1") (pin "9") (pinfunction "PC3_9") (pintype "bidirectional"))
      (node (ref "R38") (pin "1") (pinfunction "1_1") (pintype "passive"))
      (node (ref "R41") (pin "2") (pinfunction "2_2") (pintype "passive"))
    )
    (net (code "24") (name "CH_PON_EX") (class "Default")
      (node (ref "CON1") (pin "2") (pinfunction "2_2") (pintype "passive"))
      (node (ref "IC12") (pin "P$4") (pinfunction "D_P$4") (pintype "passive"))
    )
    (net (code "25") (name "CS_B0") (class "Default")
      (node (ref "IC3") (pin "1") (pinfunction "A_1") (pintype "input"))
      (node (ref "PROZ1") (pin "43") (pinfunction "PA4_43") (pintype "bidirectional"))
    )
    (net (code "26") (name "CS_B1") (class "Default")
      (node (ref "IC3") (pin "2") (pinfunction "B_2") (pintype "input"))
      (node (ref "PROZ1") (pin "51") (pinfunction "PB15_51") (pintype "bidirectional"))
    )
    (net (code "27") (name "CS_B2") (class "Default")
      (node (ref "IC3") (pin "3") (pinfunction "C_3") (pintype "input"))
      (node (ref "PROZ1") (pin "52") (pinfunction "PC6_52") (pintype "bidirectional"))
    )
    (net (code "28") (name "GND") (class "Default")
      (node (ref "C1") (pin "2") (pinfunction "2_2") (pintype "passive"))
      (node (ref "C10") (pin "2") (pinfunction "2_2") (pintype "passive"))
      (node (ref "C11") (pin "2") (pinfunction "2_2") (pintype "passive"))
      (node (ref "C12") (pin "2") (pinfunction "2_2") (pintype "passive"))
      (node (ref "C13") (pin "2") (pinfunction "2_2") (pintype "passive"))
      (node (ref "C14") (pin "2") (pinfunction "2_2") (pintype "passive"))
      (node (ref "C15") (pin "2") (pinfunction "2_2") (pintype "passive"))
      (node (ref "C16") (pin "2") (pinfunction "2_2") (pintype "passive"))
      (node (ref "C17") (pin "2") (pinfunction "2_2") (pintype "passive"))
      (node (ref "C18") (pin "2") (pinfunction "2_2") (pintype "passive"))
      (node (ref "C19") (pin "2") (pinfunction "2_2") (pintype "passive"))
      (node (ref "C2") (pin "2") (pinfunction "2_2") (pintype "passive"))
      (node (ref "C22") (pin "2") (pinfunction "2_2") (pintype "passive"))
      (node (ref "C3") (pin "2") (pinfunction "2_2") (pintype "passive"))
      (node (ref "C4") (pin "2") (pinfunction "2_2") (pintype "passive"))
      (node (ref "C5") (pin "2") (pinfunction "2_2") (pintype "passive"))
      (node (ref "C6") (pin "2") (pinfunction "2_2") (pintype "passive"))
      (node (ref "C7") (pin "2") (pinfunction "2_2") (pintype "passive"))
      (node (ref "C8") (pin "2") (pinfunction "2_2") (pintype "passive"))
      (node (ref "C9") (pin "2") (pinfunction "2_2") (pintype "passive"))
      (node (ref "CON1") (pin "1") (pinfunction "1_1") (pintype "passive"))
      (node (ref "D1") (pin "A") (pinfunction "A_A") (pintype "passive"))
      (node (ref "D10") (pin "P$1") (pinfunction "P$1_P$1") (pintype "bidirectional"))
      (node (ref "D10") (pin "P$11") (pinfunction "P$1_P$11") (pintype "bidirectional"))
      (node (ref "D11") (pin "P$1") (pinfunction "P$1_P$1") (pintype "bidirectional"))
      (node (ref "D11") (pin "P$11") (pinfunction "P$1_P$11") (pintype "bidirectional"))
      (node (ref "D12") (pin "P$1") (pinfunction "P$1_P$1") (pintype "bidirectional"))
      (node (ref "D12") (pin "P$11") (pinfunction "P$1_P$11") (pintype "bidirectional"))
      (node (ref "D13") (pin "P$1") (pinfunction "P$1_P$1") (pintype "bidirectional"))
      (node (ref "D13") (pin "P$11") (pinfunction "P$1_P$11") (pintype "bidirectional"))
      (node (ref "D2") (pin "A") (pinfunction "A_A") (pintype "passive"))
      (node (ref "D3") (pin "3") (pinfunction "P$3_3") (pintype "passive"))
      (node (ref "D4") (pin "3") (pinfunction "P$3_3") (pintype "passive"))
      (node (ref "D5") (pin "P$1") (pinfunction "P$1_P$1") (pintype "bidirectional"))
      (node (ref "D5") (pin "P$11") (pinfunction "P$1_P$11") (pintype "bidirectional"))
      (node (ref "D6") (pin "P$1") (pinfunction "P$1_P$1") (pintype "bidirectional"))
      (node (ref "D6") (pin "P$11") (pinfunction "P$1_P$11") (pintype "bidirectional"))
      (node (ref "D7") (pin "P$1") (pinfunction "P$1_P$1") (pintype "bidirectional"))
      (node (ref "D7") (pin "P$11") (pinfunction "P$1_P$11") (pintype "bidirectional"))
      (node (ref "D8") (pin "P$1") (pinfunction "P$1_P$1") (pintype "bidirectional"))
      (node (ref "D8") (pin "P$11") (pinfunction "P$1_P$11") (pintype "bidirectional"))
      (node (ref "D9") (pin "P$1") (pinfunction "P$1_P$1") (pintype "bidirectional"))
      (node (ref "D9") (pin "P$11") (pinfunction "P$1_P$11") (pintype "bidirectional"))
      (node (ref "IC1") (pin "2") (pinfunction "GND_2") (pintype "power_in"))
      (node (ref "IC10") (pin "2") (pinfunction "GND_2") (pintype "bidirectional"))
      (node (ref "IC11") (pin "4") (pinfunction "GND_4") (pintype "power_in"))
      (node (ref "IC12") (pin "P$5") (pinfunction "S_P$5") (pintype "passive"))
      (node (ref "IC13") (pin "10") (pinfunction "GND_10") (pintype "bidirectional"))
      (node (ref "IC13") (pin "11") (pinfunction "GND_11") (pintype "bidirectional"))
      (node (ref "IC13") (pin "12") (pinfunction "GND_12") (pintype "bidirectional"))
      (node (ref "IC13") (pin "3") (pinfunction "GND_3") (pintype "bidirectional"))
      (node (ref "IC13") (pin "4") (pinfunction "GND_4") (pintype "bidirectional"))
      (node (ref "IC13") (pin "5") (pinfunction "GND_5") (pintype "bidirectional"))
      (node (ref "IC2") (pin "2") (pinfunction "GND_2") (pintype "power_in"))
      (node (ref "IC3") (pin "4") (pinfunction "G2A_4") (pintype "input"))
      (node (ref "IC3") (pin "5") (pinfunction "G2B_5") (pintype "input"))
      (node (ref "IC3") (pin "8") (pinfunction "GND_8") (pintype "power_in"))
      (node (ref "IC4") (pin "7") (pinfunction "VSS_7") (pintype "power_in"))
      (node (ref "IC5") (pin "7") (pinfunction "VSS_7") (pintype "power_in"))
      (node (ref "IC6") (pin "12") (pinfunction "GND2_12") (pintype "bidirectional"))
      (node (ref "IC6") (pin "13") (pinfunction "HEAT_13") (pintype "bidirectional"))
      (node (ref "IC6") (pin "6") (pinfunction "GND1_6") (pintype "bidirectional"))
      (node (ref "IC7") (pin "12") (pinfunction "GND2_12") (pintype "bidirectional"))
      (node (ref "IC7") (pin "13") (pinfunction "HEAT_13") (pintype "bidirectional"))
      (node (ref "IC7") (pin "6") (pinfunction "GND1_6") (pintype "bidirectional"))
      (node (ref "IC8") (pin "2") (pinfunction "GND_2") (pintype "bidirectional"))
      (node (ref "IC9") (pin "2") (pinfunction "GND_2") (pintype "bidirectional"))
      (node (ref "PROZ1") (pin "47") (pinfunction "GND_47") (pintype "passive"))
      (node (ref "PROZ1") (pin "48") (pinfunction "GND_48") (pintype "passive"))
      (node (ref "Q1") (pin "2") (pinfunction "S_2") (pintype "passive"))
      (node (ref "Q2") (pin "2") (pinfunction "S_2") (pintype "passive"))
      (node (ref "Q3") (pin "2") (pinfunction "S_2") (pintype "passive"))
      (node (ref "Q4") (pin "2") (pinfunction "S_2") (pintype "passive"))
      (node (ref "Q5") (pin "2") (pinfunction "S_2") (pintype "passive"))
      (node (ref "Q6") (pin "2") (pinfunction "S_2") (pintype "passive"))
      (node (ref "Q7") (pin "2") (pinfunction "S_2") (pintype "passive"))
      (node (ref "Q8") (pin "2") (pinfunction "S_2") (pintype "passive"))
      (node (ref "Q9") (pin "2") (pinfunction "S_2") (pintype "passive"))
      (node (ref "R1") (pin "1") (pinfunction "1_1") (pintype "passive"))
      (node (ref "R11") (pin "1") (pinfunction "1_1") (pintype "passive"))
      (node (ref "R12") (pin "1") (pinfunction "1_1") (pintype "passive"))
      (node (ref "R13") (pin "1") (pinfunction "1_1") (pintype "passive"))
      (node (ref "R14") (pin "1") (pinfunction "1_1") (pintype "passive"))
      (node (ref "R16") (pin "1") (pinfunction "1_1") (pintype "passive"))
      (node (ref "R17") (pin "1") (pinfunction "1_1") (pintype "passive"))
      (node (ref "R2") (pin "1") (pinfunction "1_1") (pintype "passive"))
      (node (ref "R20") (pin "1") (pinfunction "1_1") (pintype "passive"))
      (node (ref "R23") (pin "1") (pinfunction "1_1") (pintype "passive"))
      (node (ref "R27") (pin "2") (pinfunction "2_2") (pintype "passive"))
      (node (ref "R29") (pin "2") (pinfunction "2_2") (pintype "passive"))
      (node (ref "R3") (pin "1") (pinfunction "1_1") (pintype "passive"))
      (node (ref "R33") (pin "1") (pinfunction "1_1") (pintype "passive"))
      (node (ref "R38") (pin "2") (pinfunction "2_2") (pintype "passive"))
      (node (ref "R4") (pin "1") (pinfunction "1_1") (pintype "passive"))
      (node (ref "R9") (pin "1") (pinfunction "1_1") (pintype "passive"))
      (node (ref "TB1") (pin "GND") (pinfunction "GND_GND") (pintype "power_in"))
      (node (ref "TB1") (pin "GND2") (pinfunction "GND_GND2") (pintype "power_in"))
      (node (ref "TERA-DC/DC1") (pin "GND@1") (pinfunction "GND_GND@1") (pintype "power_in"))
      (node (ref "TERA-DC/DC1") (pin "GND@2") (pinfunction "GND_GND@2") (pintype "power_in"))
      (node (ref "X1") (pin "1") (pinfunction "1_1") (pintype "passive"))
      (node (ref "X13") (pin "1") (pinfunction "1_1") (pintype "passive"))
      (node (ref "X14") (pin "1") (pinfunction "1_1") (pintype "passive"))
      (node (ref "X15") (pin "1") (pinfunction "1_1") (pintype "passive"))
      (node (ref "X2") (pin "2") (pinfunction "3V3_2") (pintype "passive"))
      (node (ref "X3") (pin "1") (pinfunction "GND_1") (pintype "passive"))
      (node (ref "X4") (pin "1") (pinfunction "GND_1") (pintype "passive"))
      (node (ref "X5") (pin "P$1") (pinfunction "1_P$1") (pintype "bidirectional"))
      (node (ref "X6") (pin "P$1") (pinfunction "1_P$1") (pintype "bidirectional"))
      (node (ref "X7") (pin "P$1") (pinfunction "1_P$1") (pintype "bidirectional"))
      (node (ref "X8") (pin "P$1") (pinfunction "1_P$1") (pintype "bidirectional"))
    )
    (net (code "29") (name "HS_CO1") (class "Default")
      (node (ref "IC7") (pin "4") (pinfunction "CO1_4") (pintype "bidirectional"))
      (node (ref "PROZ1") (pin "36") (pinfunction "PB2_36") (pintype "bidirectional"))
    )
    (net (code "30") (name "HS_RM") (class "Default")
      (node (ref "PROZ1") (pin "37") (pinfunction "PB1_37") (pintype "bidirectional"))
      (node (ref "Q4") (pin "3") (pinfunction "D_3") (pintype "passive"))
      (node (ref "R21") (pin "1") (pinfunction "1_1") (pintype "passive"))
    )
    (net (code "31") (name "HS_RM_EX") (class "Default")
      (node (ref "R22") (pin "2") (pinfunction "2_2") (pintype "passive"))
      (node (ref "R23") (pin "2") (pinfunction "2_2") (pintype "passive"))
      (node (ref "X11") (pin "P$3") (pinfunction "3_P$3") (pintype "bidirectional"))
    )
    (net (code "32") (name "IL1") (class "Default")
      (node (ref "IC5") (pin "12") (pinfunction "I1_12") (pintype "input"))
      (node (ref "IC5") (pin "13") (pinfunction "I2_13") (pintype "input"))
      (node (ref "PROZ1") (pin "14") (pinfunction "PB6_14") (pintype "bidirectional"))
      (node (ref "R9") (pin "2") (pinfunction "2_2") (pintype "passive"))
    )
    (net (code "33") (name "IL2") (class "Default")
      (node (ref "IC5") (pin "4") (pinfunction "I1_4") (pintype "input"))
      (node (ref "IC5") (pin "5") (pinfunction "I2_5") (pintype "input"))
      (node (ref "PROZ1") (pin "12") (pinfunction "PB7_12") (pintype "bidirectional"))
      (node (ref "R13") (pin "2") (pinfunction "2_2") (pintype "passive"))
    )
    (net (code "34") (name "ILK1") (class "Default")
      (node (ref "CON1") (pin "8") (pinfunction "8_8") (pintype "passive"))
      (node (ref "IC4") (pin "11") (pinfunction "I0_11") (pintype "input"))
      (node (ref "JP1") (pin "2") (pinfunction "2_2") (pintype "passive"))
      (node (ref "Q1") (pin "3") (pinfunction "D_3") (pintype "passive"))
      (node (ref "SJ1") (pin "2") (pinfunction "2_2") (pintype "passive"))
    )
    (net (code "35") (name "ILK1_CH") (class "Default")
      (node (ref "CON1") (pin "7") (pinfunction "7_7") (pintype "passive"))
      (node (ref "SJ1") (pin "1") (pinfunction "1_1") (pintype "passive"))
      (node (ref "X8") (pin "P$3") (pinfunction "3_P$3") (pintype "bidirectional"))
    )
    (net (code "36") (name "ILK2") (class "Default")
      (node (ref "IC4") (pin "12") (pinfunction "I1_12") (pintype "input"))
      (node (ref "IC4") (pin "13") (pinfunction "I2_13") (pintype "input"))
      (node (ref "JP2") (pin "2") (pinfunction "2_2") (pintype "passive"))
      (node (ref "Q2") (pin "3") (pinfunction "D_3") (pintype "passive"))
      (node (ref "X8") (pin "P$2") (pinfunction "2_P$2") (pintype "bidirectional"))
    )
    (net (code "37") (name "INTERLOCK_OK") (class "Default")
      (node (ref "IC4") (pin "10") (pinfunction "O_10") (pintype "output"))
      (node (ref "IC6") (pin "1") (pinfunction "IN2_1") (pintype "bidirectional"))
      (node (ref "IC6") (pin "7") (pinfunction "IN1_7") (pintype "bidirectional"))
      (node (ref "IC7") (pin "1") (pinfunction "IN2_1") (pintype "bidirectional"))
      (node (ref "IC7") (pin "7") (pinfunction "IN1_7") (pintype "bidirectional"))
      (node (ref "LED5") (pin "A") (pinfunction "A_A") (pintype "passive"))
      (node (ref "PROZ1") (pin "44") (pinfunction "PA3_44") (pintype "bidirectional"))
    )
    (net (code "38") (name "JTCK") (class "Default")
      (node (ref "PROZ1") (pin "18") (pinfunction "PA14_18") (pintype "bidirectional"))
      (node (ref "X2") (pin "5") (pinfunction "JTCK_5") (pintype "passive"))
    )
    (net (code "39") (name "JTDI") (class "Default")
      (node (ref "PROZ1") (pin "16") (pinfunction "PA15_16") (pintype "bidirectional"))
      (node (ref "X2") (pin "6") (pinfunction "JTDI_6") (pintype "passive"))
    )
    (net (code "40") (name "JTDO") (class "Default")
      (node (ref "PROZ1") (pin "20") (pinfunction "PB3_20") (pintype "bidirectional"))
      (node (ref "X2") (pin "7") (pinfunction "JTDO_7") (pintype "passive"))
    )
    (net (code "41") (name "JTMS") (class "Default")
      (node (ref "PROZ1") (pin "59") (pinfunction "PA13_59") (pintype "bidirectional"))
      (node (ref "X2") (pin "3") (pinfunction "JTMS_3") (pintype "passive"))
    )
    (net (code "42") (name "JTNRST") (class "Default")
      (node (ref "PROZ1") (pin "22") (pinfunction "PB4_22") (pintype "bidirectional"))
      (node (ref "X2") (pin "8") (pinfunction "JTNRST_8") (pintype "passive"))
    )
    (net (code "43") (name "LED1") (class "Default")
      (node (ref "PROZ1") (pin "25") (pinfunction "PB5_25") (pintype "bidirectional"))
    )
    (net (code "44") (name "LED2") (class "Default")
      (node (ref "PROZ1") (pin "27") (pinfunction "PD2_27") (pintype "bidirectional"))
    )
    (net (code "45") (name "LED3") (class "Default")
      (node (ref "PROZ1") (pin "29") (pinfunction "PC12_29") (pintype "bidirectional"))
    )
    (net (code "46") (name "LEM_1") (class "Default")
      (node (ref "C18") (pin "1") (pinfunction "1_1") (pintype "passive"))
      (node (ref "D7") (pin "P$2") (pinfunction "P$2_P$2") (pintype "bidirectional"))
      (node (ref "PROZ1") (pin "15") (pinfunction "PC0_15") (pintype "bidirectional"))
      (node (ref "R26") (pin "2") (pinfunction "2_2") (pintype "passive"))
    )
    (net (code "47") (name "LEM_2") (class "Default")
      (node (ref "C17") (pin "1") (pinfunction "1_1") (pintype "passive"))
      (node (ref "D6") (pin "P$2") (pinfunction "P$2_P$2") (pintype "bidirectional"))
      (node (ref "PROZ1") (pin "13") (pinfunction "PC1_13") (pintype "bidirectional"))
      (node (ref "R25") (pin "2") (pinfunction "2_2") (pintype "passive"))
    )
    (net (code "48") (name "LEM_3") (class "Default")
      (node (ref "C16") (pin "1") (pinfunction "1_1") (pintype "passive"))
      (node (ref "D8") (pin "P$2") (pinfunction "P$2_P$2") (pintype "bidirectional"))
      (node (ref "PROZ1") (pin "11") (pinfunction "PC2_11") (pintype "bidirectional"))
      (node (ref "R24") (pin "2") (pinfunction "2_2") (pintype "passive"))
    )
    (net (code "49") (name "LK_1") (class "Default")
      (node (ref "IC13") (pin "9") (pinfunction "IN1_9") (pintype "bidirectional"))
      (node (ref "PROZ1") (pin "23") (pinfunction "PC13_23") (pintype "bidirectional"))
    )
    (net (code "50") (name "LK_2") (class "Default")
      (node (ref "IC13") (pin "6") (pinfunction "IN2_6") (pintype "bidirectional"))
      (node (ref "PROZ1") (pin "21") (pinfunction "PC14_21") (pintype "bidirectional"))
    )
    (net (code "51") (name "LK_EF") (class "Default")
      (node (ref "IC13") (pin "8") (pinfunction "EF_8") (pintype "bidirectional"))
      (node (ref "PROZ1") (pin "8") (pinfunction "PB9_8") (pintype "bidirectional"))
      (node (ref "R46") (pin "1") (pinfunction "1_1") (pintype "passive"))
    )
    (net (code "52") (name "LK_ON") (class "Default")
      (node (ref "IC13") (pin "7") (pinfunction "INH_7") (pintype "bidirectional"))
      (node (ref "PROZ1") (pin "10") (pinfunction "PB8_10") (pintype "bidirectional"))
    )
    (net (code "53") (name "LK_RM") (class "Default")
      (node (ref "PROZ1") (pin "58") (pinfunction "PA10_58") (pintype "bidirectional"))
      (node (ref "Q5") (pin "3") (pinfunction "D_3") (pintype "passive"))
      (node (ref "R31") (pin "1") (pinfunction "1_1") (pintype "passive"))
    )
    (net (code "54") (name "MISO") (class "Default")
      (node (ref "IC6") (pin "11") (pinfunction "MISO/ST2_11") (pintype "bidirectional"))
      (node (ref "IC7") (pin "11") (pinfunction "MISO/ST2_11") (pintype "bidirectional"))
      (node (ref "R48") (pin "2") (pinfunction "2_2") (pintype "passive"))
      (node (ref "X5") (pin "P$4") (pinfunction "4_P$4") (pintype "bidirectional"))
      (node (ref "X6") (pin "P$4") (pinfunction "4_P$4") (pintype "bidirectional"))
      (node (ref "X7") (pin "P$4") (pinfunction "4_P$4") (pintype "bidirectional"))
    )
    (net (code "55") (name "MISO_S") (class "Default")
      (node (ref "D12") (pin "P$2") (pinfunction "P$2_P$2") (pintype "bidirectional"))
      (node (ref "PROZ1") (pin "42") (pinfunction "PA6_42") (pintype "bidirectional"))
      (node (ref "R48") (pin "1") (pinfunction "1_1") (pintype "passive"))
    )
    (net (code "56") (name "MOSI") (class "Default")
      (node (ref "IC6") (pin "2") (pinfunction "MOSI_2") (pintype "bidirectional"))
      (node (ref "IC7") (pin "2") (pinfunction "MOSI_2") (pintype "bidirectional"))
      (node (ref "R49") (pin "2") (pinfunction "2_2") (pintype "passive"))
      (node (ref "X5") (pin "P$3") (pinfunction "3_P$3") (pintype "bidirectional"))
      (node (ref "X6") (pin "P$3") (pinfunction "3_P$3") (pintype "bidirectional"))
      (node (ref "X7") (pin "P$3") (pinfunction "3_P$3") (pintype "bidirectional"))
    )
    (net (code "57") (name "MOSI_S") (class "Default")
      (node (ref "D13") (pin "P$2") (pinfunction "P$2_P$2") (pintype "bidirectional"))
      (node (ref "PROZ1") (pin "41") (pinfunction "PA7_41") (pintype "bidirectional"))
      (node (ref "R49") (pin "1") (pinfunction "1_1") (pintype "passive"))
    )
    (net (code "58") (name "NALERT") (class "Default")
      (node (ref "IC4") (pin "9") (pinfunction "O_9") (pintype "output"))
      (node (ref "LED4") (pin "A") (pinfunction "A_A") (pintype "passive"))
      (node (ref "PROZ1") (pin "35") (pinfunction "PB10_35") (pintype "bidirectional"))
    )
    (net (code "59") (name "NALERT1") (class "Default")
      (node (ref "IC4") (pin "1") (pinfunction "I0_1") (pintype "input"))
      (node (ref "X5") (pin "P$7") (pinfunction "7_P$7") (pintype "bidirectional"))
    )
    (net (code "60") (name "NALERT2") (class "Default")
      (node (ref "IC4") (pin "2") (pinfunction "I1_2") (pintype "input"))
      (node (ref "X6") (pin "P$7") (pinfunction "7_P$7") (pintype "bidirectional"))
    )
    (net (code "61") (name "NALERT3") (class "Default")
      (node (ref "IC4") (pin "8") (pinfunction "I2_8") (pintype "input"))
      (node (ref "X7") (pin "P$7") (pinfunction "7_P$7") (pintype "bidirectional"))
    )
    (net (code "62") (name "NCS1") (class "Default")
      (node (ref "IC3") (pin "15") (pinfunction "Y0_15") (pintype "output"))
      (node (ref "X5") (pin "P$2") (pinfunction "2_P$2") (pintype "bidirectional"))
    )
    (net (code "63") (name "NCS2") (class "Default")
      (node (ref "IC3") (pin "14") (pinfunction "Y1_14") (pintype "output"))
      (node (ref "X6") (pin "P$2") (pinfunction "2_P$2") (pintype "bidirectional"))
    )
    (net (code "64") (name "NCS3") (class "Default")
      (node (ref "IC3") (pin "13") (pinfunction "Y2_13") (pintype "output"))
      (node (ref "X7") (pin "P$2") (pinfunction "2_P$2") (pintype "bidirectional"))
    )
    (net (code "65") (name "NCS4") (class "Default")
      (node (ref "IC3") (pin "12") (pinfunction "Y3_12") (pintype "output"))
      (node (ref "IC7") (pin "8") (pinfunction "NCS_8") (pintype "bidirectional"))
    )
    (net (code "66") (name "NCS5") (class "Default")
      (node (ref "IC3") (pin "11") (pinfunction "Y4_11") (pintype "output"))
      (node (ref "IC6") (pin "8") (pinfunction "NCS_8") (pintype "bidirectional"))
    )
    (net (code "67") (name "NCS6") (class "Default")
      (node (ref "IC3") (pin "10") (pinfunction "Y5_10") (pintype "output"))
    )
    (net (code "68") (name "NCS7") (class "Default")
      (node (ref "IC3") (pin "9") (pinfunction "Y6_9") (pintype "output"))
    )
    (net (code "69") (name "NCS8") (class "Default")
      (node (ref "IC3") (pin "7") (pinfunction "Y7_7") (pintype "output"))
    )
    (net (code "70") (name "NFAULT") (class "Default")
      (node (ref "IC4") (pin "6") (pinfunction "O_6") (pintype "output"))
      (node (ref "IC5") (pin "11") (pinfunction "I0_11") (pintype "input"))
      (node (ref "IC5") (pin "3") (pinfunction "I0_3") (pintype "input"))
      (node (ref "LED3") (pin "A") (pinfunction "A_A") (pintype "passive"))
      (node (ref "PROZ1") (pin "53") (pinfunction "PC7_53") (pintype "bidirectional"))
    )
    (net (code "71") (name "NFAULT1") (class "Default")
      (node (ref "IC4") (pin "3") (pinfunction "I0_3") (pintype "input"))
      (node (ref "X5") (pin "P$6") (pinfunction "6_P$6") (pintype "bidirectional"))
    )
    (net (code "72") (name "NFAULT2") (class "Default")
      (node (ref "IC4") (pin "4") (pinfunction "I1_4") (pintype "input"))
      (node (ref "X6") (pin "P$6") (pinfunction "6_P$6") (pintype "bidirectional"))
    )
    (net (code "73") (name "NFAULT3") (class "Default")
      (node (ref "IC4") (pin "5") (pinfunction "I2_5") (pintype "input"))
      (node (ref "X7") (pin "P$6") (pinfunction "6_P$6") (pintype "bidirectional"))
    )
    (net (code "74") (name "NRST") (class "Default")
      (node (ref "PROZ1") (pin "17") (pinfunction "NRST_17") (pintype "bidirectional"))
      (node (ref "X2") (pin "4") (pinfunction "NRST_4") (pintype "passive"))
    )
    (net (code "75") (name "Net-(C4-Pad1)") (class "Default")
      (node (ref "C4") (pin "1") (pinfunction "1_1") (pintype "passive"))
      (node (ref "R5") (pin "1") (pinfunction "1_1") (pintype "passive"))
      (node (ref "R6") (pin "1") (pinfunction "1_1") (pintype "passive"))
    )
    (net (code "76") (name "Net-(C5-Pad1)") (class "Default")
      (node (ref "C5") (pin "1") (pinfunction "1_1") (pintype "passive"))
      (node (ref "R7") (pin "1") (pinfunction "1_1") (pintype "passive"))
      (node (ref "R8") (pin "1") (pinfunction "1_1") (pintype "passive"))
    )
    (net (code "77") (name "Net-(IC1-RS)") (class "Default")
      (node (ref "IC1") (pin "8") (pinfunction "RS_8") (pintype "passive"))
      (node (ref "R3") (pin "2") (pinfunction "2_2") (pintype "passive"))
    )
    (net (code "78") (name "Net-(IC2-RS)") (class "Default")
      (node (ref "IC2") (pin "8") (pinfunction "RS_8") (pintype "passive"))
      (node (ref "R4") (pin "2") (pinfunction "2_2") (pintype "passive"))
    )
    (net (code "79") (name "Net-(IC2-VCC)") (class "Default")
      (node (ref "C2") (pin "1") (pinfunction "1_1") (pintype "passive"))
      (node (ref "IC2") (pin "3") (pinfunction "VCC_3") (pintype "power_in"))
      (node (ref "S_CAN1") (pin "P$2") (pinfunction "P$2_P$2") (pintype "bidirectional"))
    )
    (net (code "80") (name "Net-(IC5B-O)") (class "Default")
      (node (ref "IC5") (pin "6") (pinfunction "O_6") (pintype "output"))
      (node (ref "Q2") (pin "1") (pinfunction "G_1") (pintype "passive"))
    )
    (net (code "81") (name "Net-(IC5C-O)") (class "Default")
      (node (ref "IC5") (pin "10") (pinfunction "O_10") (pintype "output"))
      (node (ref "Q1") (pin "1") (pinfunction "G_1") (pintype "passive"))
    )
    (net (code "82") (name "Net-(IC6-OUT1)") (class "Default")
      (node (ref "IC6") (pin "9") (pinfunction "OUT1_9") (pintype "bidirectional"))
      (node (ref "X10") (pin "P$1") (pinfunction "1_P$1") (pintype "bidirectional"))
    )
    (net (code "83") (name "Net-(IC6-OUT2)") (class "Default")
      (node (ref "IC6") (pin "3") (pinfunction "OUT2_3") (pintype "bidirectional"))
      (node (ref "X9") (pin "P$1") (pinfunction "1_P$1") (pintype "bidirectional"))
    )
    (net (code "84") (name "Net-(IC7-OUT1)") (class "Default")
      (node (ref "IC7") (pin "9") (pinfunction "OUT1_9") (pintype "bidirectional"))
      (node (ref "X12") (pin "P$1") (pinfunction "1_P$1") (pintype "bidirectional"))
    )
    (net (code "85") (name "Net-(IC7-OUT2)") (class "Default")
      (node (ref "IC7") (pin "3") (pinfunction "OUT2_3") (pintype "bidirectional"))
      (node (ref "X11") (pin "P$1") (pinfunction "1_P$1") (pintype "bidirectional"))
    )
    (net (code "86") (name "Net-(IC8-VREF)") (class "Default")
      (node (ref "C13") (pin "1") (pinfunction "1_1") (pintype "passive"))
      (node (ref "IC8") (pin "5") (pinfunction "VREF_5") (pintype "bidirectional"))
      (node (ref "X13") (pin "3") (pinfunction "3_3") (pintype "passive"))
    )
    (net (code "87") (name "Net-(IC9-VREF)") (class "Default")
      (node (ref "C14") (pin "1") (pinfunction "1_1") (pintype "passive"))
      (node (ref "IC9") (pin "5") (pinfunction "VREF_5") (pintype "bidirectional"))
      (node (ref "X14") (pin "3") (pinfunction "3_3") (pintype "passive"))
    )
    (net (code "88") (name "Net-(IC10-VREF)") (class "Default")
      (node (ref "C15") (pin "1") (pinfunction "1_1") (pintype "passive"))
      (node (ref "IC10") (pin "5") (pinfunction "VREF_5") (pintype "bidirectional"))
      (node (ref "X15") (pin "3") (pinfunction "3_3") (pintype "passive"))
    )
    (net (code "89") (name "Net-(IC12A-D)") (class "Default")
      (node (ref "IC12") (pin "P$6") (pinfunction "D_P$6") (pintype "passive"))
      (node (ref "R44") (pin "1") (pinfunction "1_1") (pintype "passive"))
      (node (ref "R45") (pin "2") (pinfunction "2_2") (pintype "passive"))
    )
    (net (code "90") (name "Net-(IC12A-G)") (class "Default")
      (node (ref "IC12") (pin "P$1") (pinfunction "G_P$1") (pintype "passive"))
      (node (ref "R41") (pin "1") (pinfunction "1_1") (pintype "passive"))
    )
    (net (code "91") (name "Net-(IC12B-G)") (class "Default")
      (node (ref "IC12") (pin "P$3") (pinfunction "G_P$3") (pintype "passive"))
      (node (ref "R45") (pin "1") (pinfunction "1_1") (pintype "passive"))
    )
    (net (code "92") (name "Net-(IC13-OUT1)") (class "Default")
      (node (ref "IC13") (pin "13") (pinfunction "OUT1_13") (pintype "bidirectional"))
      (node (ref "X17") (pin "P$2") (pinfunction "2_P$2") (pintype "bidirectional"))
    )
    (net (code "93") (name "Net-(IC13-OUT2)") (class "Default")
      (node (ref "IC13") (pin "2") (pinfunction "OUT2_2") (pintype "bidirectional"))
      (node (ref "X17") (pin "P$1") (pinfunction "1_P$1") (pintype "bidirectional"))
    )
    (net (code "94") (name "Net-(JP1-Pad1)") (class "Default")
      (node (ref "JP1") (pin "1") (pinfunction "1_1") (pintype "passive"))
      (node (ref "R10") (pin "1") (pinfunction "1_1") (pintype "passive"))
    )
    (net (code "95") (name "Net-(JP1-Pad3)") (class "Default")
      (node (ref "JP1") (pin "3") (pinfunction "3_3") (pintype "passive"))
      (node (ref "R11") (pin "2") (pinfunction "2_2") (pintype "passive"))
    )
    (net (code "96") (name "Net-(JP2-Pad1)") (class "Default")
      (node (ref "JP2") (pin "1") (pinfunction "1_1") (pintype "passive"))
      (node (ref "R15") (pin "1") (pinfunction "1_1") (pintype "passive"))
    )
    (net (code "97") (name "Net-(JP2-Pad3)") (class "Default")
      (node (ref "JP2") (pin "3") (pinfunction "3_3") (pintype "passive"))
      (node (ref "R16") (pin "2") (pinfunction "2_2") (pintype "passive"))
    )
    (net (code "98") (name "Net-(LED1-PadC)") (class "Default")
      (node (ref "LED1") (pin "C") (pinfunction "C_C") (pintype "passive"))
      (node (ref "R1") (pin "2") (pinfunction "2_2") (pintype "passive"))
    )
    (net (code "99") (name "Net-(LED2-PadC)") (class "Default")
      (node (ref "LED2") (pin "C") (pinfunction "C_C") (pintype "passive"))
      (node (ref "R2") (pin "2") (pinfunction "2_2") (pintype "passive"))
    )
    (net (code "100") (name "Net-(LED3-PadC)") (class "Default")
      (node (ref "LED3") (pin "C") (pinfunction "C_C") (pintype "passive"))
      (node (ref "R12") (pin "2") (pinfunction "2_2") (pintype "passive"))
    )
    (net (code "101") (name "Net-(LED4-PadC)") (class "Default")
      (node (ref "LED4") (pin "C") (pinfunction "C_C") (pintype "passive"))
      (node (ref "R14") (pin "2") (pinfunction "2_2") (pintype "passive"))
    )
    (net (code "102") (name "Net-(LED5-PadC)") (class "Default")
      (node (ref "LED5") (pin "C") (pinfunction "C_C") (pintype "passive"))
      (node (ref "R17") (pin "2") (pinfunction "2_2") (pintype "passive"))
    )
    (net (code "103") (name "Net-(Q3-G)") (class "Default")
      (node (ref "Q3") (pin "1") (pinfunction "G_1") (pintype "passive"))
      (node (ref "R19") (pin "1") (pinfunction "1_1") (pintype "passive"))
    )
    (net (code "104") (name "Net-(Q4-G)") (class "Default")
      (node (ref "Q4") (pin "1") (pinfunction "G_1") (pintype "passive"))
      (node (ref "R22") (pin "1") (pinfunction "1_1") (pintype "passive"))
    )
    (net (code "105") (name "Net-(Q5-G)") (class "Default")
      (node (ref "Q5") (pin "1") (pinfunction "G_1") (pintype "passive"))
      (node (ref "R32") (pin "1") (pinfunction "1_1") (pintype "passive"))
    )
    (net (code "106") (name "Net-(Q6-G)") (class "Default")
      (node (ref "Q6") (pin "1") (pinfunction "G_1") (pintype "passive"))
      (node (ref "R36") (pin "1") (pinfunction "1_1") (pintype "passive"))
    )
    (net (code "107") (name "Net-(Q7-G)") (class "Default")
      (node (ref "Q7") (pin "1") (pinfunction "G_1") (pintype "passive"))
      (node (ref "R37") (pin "1") (pinfunction "1_1") (pintype "passive"))
    )
    (net (code "108") (name "Net-(Q8-G)") (class "Default")
      (node (ref "Q8") (pin "1") (pinfunction "G_1") (pintype "passive"))
      (node (ref "R39") (pin "1") (pinfunction "1_1") (pintype "passive"))
    )
    (net (code "109") (name "Net-(Q9-G)") (class "Default")
      (node (ref "Q9") (pin "1") (pinfunction "G_1") (pintype "passive"))
      (node (ref "R40") (pin "1") (pinfunction "1_1") (pintype "passive"))
    )
    (net (code "110") (name "Net-(R5-Pad2)") (class "Default")
      (node (ref "R5") (pin "2") (pinfunction "2_2") (pintype "passive"))
      (node (ref "S_CAN2_ROFF") (pin "P$2") (pinfunction "P$2_P$2") (pintype "bidirectional"))
    )
    (net (code "111") (name "Net-(R7-Pad2)") (class "Default")
      (node (ref "R7") (pin "2") (pinfunction "2_2") (pintype "passive"))
      (node (ref "S_CAN1_ROFF") (pin "P$2") (pinfunction "P$2_P$2") (pintype "bidirectional"))
    )
    (net (code "112") (name "Net-(R24-Pad1)") (class "Default")
      (node (ref "R24") (pin "1") (pinfunction "1_1") (pintype "passive"))
      (node (ref "X13") (pin "2") (pinfunction "2_2") (pintype "passive"))
    )
    (net (code "113") (name "Net-(R25-Pad1)") (class "Default")
      (node (ref "R25") (pin "1") (pinfunction "1_1") (pintype "passive"))
      (node (ref "X14") (pin "2") (pinfunction "2_2") (pintype "passive"))
    )
    (net (code "114") (name "Net-(R26-Pad1)") (class "Default")
      (node (ref "R26") (pin "1") (pinfunction "1_1") (pintype "passive"))
      (node (ref "X15") (pin "2") (pinfunction "2_2") (pintype "passive"))
    )
    (net (code "115") (name "Net-(R28-Pad1)") (class "Default")
      (node (ref "R28") (pin "1") (pinfunction "1_1") (pintype "passive"))
      (node (ref "X16") (pin "1") (pinfunction "1_1") (pintype "passive"))
    )
    (net (code "116") (name "Net-(R30-Pad1)") (class "Default")
      (node (ref "R30") (pin "1") (pinfunction "1_1") (pintype "passive"))
      (node (ref "X16") (pin "3") (pinfunction "3_3") (pintype "passive"))
    )
    (net (code "117") (name "Net-(X10-3)") (class "Default")
      (node (ref "X10") (pin "P$3") (pinfunction "3_P$3") (pintype "bidirectional"))
      (node (ref "X9") (pin "P$4") (pinfunction "4_P$4") (pintype "bidirectional"))
    )
    (net (code "118") (name "Net-(X11-4)") (class "Default")
      (node (ref "X11") (pin "P$4") (pinfunction "4_P$4") (pintype "bidirectional"))
      (node (ref "X12") (pin "P$3") (pinfunction "3_P$3") (pintype "bidirectional"))
    )
    (net (code "119") (name "Net-(X17-3)") (class "Default")
      (node (ref "R32") (pin "2") (pinfunction "2_2") (pintype "passive"))
      (node (ref "R33") (pin "2") (pinfunction "2_2") (pintype "passive"))
      (node (ref "X17") (pin "P$3") (pinfunction "3_P$3") (pintype "bidirectional"))
    )
    (net (code "120") (name "PB11") (class "Default")
      (node (ref "PROZ1") (pin "34") (pinfunction "PB11_34") (pintype "bidirectional"))
    )
    (net (code "121") (name "PB14") (class "Default")
      (node (ref "PROZ1") (pin "33") (pinfunction "PB14_33") (pintype "bidirectional"))
    )
    (net (code "122") (name "PC8") (class "Default")
      (node (ref "PROZ1") (pin "54") (pinfunction "PC8_54") (pintype "bidirectional"))
    )
    (net (code "123") (name "PC9") (class "Default")
      (node (ref "PROZ1") (pin "55") (pinfunction "PC9_55") (pintype "bidirectional"))
    )
    (net (code "124") (name "SCLK") (class "Default")
      (node (ref "IC6") (pin "5") (pinfunction "SCLK_5") (pintype "bidirectional"))
      (node (ref "IC7") (pin "5") (pinfunction "SCLK_5") (pintype "bidirectional"))
      (node (ref "R47") (pin "2") (pinfunction "2_2") (pintype "passive"))
      (node (ref "X5") (pin "P$5") (pinfunction "5_P$5") (pintype "bidirectional"))
      (node (ref "X6") (pin "P$5") (pinfunction "5_P$5") (pintype "bidirectional"))
      (node (ref "X7") (pin "P$5") (pinfunction "5_P$5") (pintype "bidirectional"))
    )
    (net (code "125") (name "SCLK_S") (class "Default")
      (node (ref "D11") (pin "P$2") (pinfunction "P$2_P$2") (pintype "bidirectional"))
      (node (ref "PROZ1") (pin "60") (pinfunction "PA5_60") (pintype "bidirectional"))
      (node (ref "R47") (pin "1") (pinfunction "1_1") (pintype "passive"))
    )
    (net (code "126") (name "SLS_CO1") (class "Default")
      (node (ref "IC6") (pin "4") (pinfunction "CO1_4") (pintype "bidirectional"))
      (node (ref "PROZ1") (pin "57") (pinfunction "PA9_57") (pintype "bidirectional"))
    )
    (net (code "127") (name "SLS_RM") (class "Default")
      (node (ref "PROZ1") (pin "56") (pinfunction "PA8_56") (pintype "bidirectional"))
      (node (ref "Q3") (pin "3") (pinfunction "D_3") (pintype "passive"))
      (node (ref "R18") (pin "1") (pinfunction "1_1") (pintype "passive"))
    )
    (net (code "128") (name "SLS_RM_EX") (class "Default")
      (node (ref "R19") (pin "2") (pinfunction "2_2") (pintype "passive"))
      (node (ref "R20") (pin "2") (pinfunction "2_2") (pintype "passive"))
      (node (ref "X9") (pin "P$3") (pinfunction "3_P$3") (pintype "bidirectional"))
    )
    (net (code "129") (name "SPI_CS") (class "Default")
      (node (ref "IC3") (pin "6") (pinfunction "G1_6") (pintype "input"))
      (node (ref "PROZ1") (pin "38") (pinfunction "PB0_38") (pintype "bidirectional"))
    )
    (net (code "130") (name "TS1") (class "Default")
      (node (ref "C21") (pin "2") (pinfunction "2_2") (pintype "passive"))
      (node (ref "D9") (pin "P$2") (pinfunction "P$2_P$2") (pintype "bidirectional"))
      (node (ref "PROZ1") (pin "40") (pinfunction "PC4_40") (pintype "bidirectional"))
      (node (ref "R29") (pin "1") (pinfunction "1_1") (pintype "passive"))
      (node (ref "R30") (pin "2") (pinfunction "2_2") (pintype "passive"))
    )
    (net (code "131") (name "TS2") (class "Default")
      (node (ref "C20") (pin "2") (pinfunction "2_2") (pintype "passive"))
      (node (ref "D10") (pin "P$2") (pinfunction "P$2_P$2") (pintype "bidirectional"))
      (node (ref "PROZ1") (pin "39") (pinfunction "PC5_39") (pintype "bidirectional"))
      (node (ref "R27") (pin "1") (pinfunction "1_1") (pintype "passive"))
      (node (ref "R28") (pin "2") (pinfunction "2_2") (pintype "passive"))
    )
    (net (code "132") (name "USART_RXD") (class "Default")
      (node (ref "PROZ1") (pin "30") (pinfunction "PC11_30") (pintype "bidirectional"))
      (node (ref "X2") (pin "10") (pinfunction "RXD_10") (pintype "passive"))
    )
    (net (code "133") (name "USART_TXD") (class "Default")
      (node (ref "PROZ1") (pin "28") (pinfunction "PC10_28") (pintype "bidirectional"))
      (node (ref "X2") (pin "9") (pinfunction "TXD_9") (pintype "passive"))
    )
    (net (code "134") (name "VBAT") (class "Default")
      (node (ref "C19") (pin "1") (pinfunction "1_1") (pintype "passive"))
      (node (ref "D1") (pin "C") (pinfunction "C_C") (pintype "passive"))
      (node (ref "D2") (pin "C") (pinfunction "C_C") (pintype "passive"))
      (node (ref "IC11") (pin "2") (pinfunction "VIN_2") (pintype "passive"))
      (node (ref "IC12") (pin "P$2") (pinfunction "S_P$2") (pintype "passive"))
      (node (ref "IC13") (pin "1") (pinfunction "VS_1") (pintype "bidirectional"))
      (node (ref "R42") (pin "2") (pinfunction "2_2") (pintype "passive"))
      (node (ref "R43") (pin "2") (pinfunction "2_2") (pintype "passive"))
      (node (ref "R44") (pin "2") (pinfunction "2_2") (pintype "passive"))
      (node (ref "TB1") (pin "VIN") (pinfunction "VIN_VIN") (pintype "passive"))
      (node (ref "TERA-DC/DC1") (pin "VIN") (pinfunction "VIN_VIN") (pintype "passive"))
      (node (ref "X1") (pin "2") (pinfunction "1_2") (pintype "passive"))
      (node (ref "X10") (pin "P$2") (pinfunction "2_P$2") (pintype "bidirectional"))
      (node (ref "X10") (pin "P$4") (pinfunction "4_P$4") (pintype "bidirectional"))
      (node (ref "X11") (pin "P$2") (pinfunction "2_P$2") (pintype "bidirectional"))
      (node (ref "X12") (pin "P$2") (pinfunction "2_P$2") (pintype "bidirectional"))
      (node (ref "X12") (pin "P$4") (pinfunction "4_P$4") (pintype "bidirectional"))
      (node (ref "X17") (pin "P$4") (pinfunction "4_P$4") (pintype "bidirectional"))
      (node (ref "X3") (pin "4") (pinfunction "V+_4") (pintype "passive"))
      (node (ref "X4") (pin "4") (pinfunction "V+_4") (pintype "passive"))
      (node (ref "X9") (pin "P$2") (pinfunction "2_P$2") (pintype "bidirectional"))
    )
    (net (code "135") (name "VREF_PTC_CH") (class "Default")
      (node (ref "C20") (pin "1") (pinfunction "1_1") (pintype "passive"))
      (node (ref "C21") (pin "1") (pinfunction "1_1") (pintype "passive"))
      (node (ref "C22") (pin "1") (pinfunction "1_1") (pintype "passive"))
      (node (ref "IC11") (pin "6") (pinfunction "VOUT_6") (pintype "bidirectional"))
      (node (ref "X16") (pin "2") (pinfunction "2_2") (pintype "passive"))
      (node (ref "X16") (pin "4") (pinfunction "4_4") (pintype "passive"))
    )
    (net (code "136") (name "unconnected-(IC1-VREF-Pad5)") (class "Default")
      (node (ref "IC1") (pin "5") (pinfunction "VREF_5") (pintype "passive"))
    )
    (net (code "137") (name "unconnected-(IC2-VREF-Pad5)") (class "Default")
      (node (ref "IC2") (pin "5") (pinfunction "VREF_5") (pintype "passive"))
    )
    (net (code "138") (name "unconnected-(IC11-~{SHDN}-Pad3)") (class "Default")
      (node (ref "IC11") (pin "3") (pinfunction "~{SHDN}_3") (pintype "passive"))
    )
    (net (code "139") (name "unconnected-(PROZ1F-AGND-Pad1)") (class "Default")
      (node (ref "PROZ1") (pin "1") (pinfunction "AGND_1") (pintype "passive"))
    )
    (net (code "140") (name "unconnected-(PROZ1F-VBAT-Pad6)") (class "Default")
      (node (ref "PROZ1") (pin "6") (pinfunction "VBAT_6") (pintype "passive"))
    )
    (net (code "141") (name "unconnected-(PROZ1F-VDDA_IN-Pad2)") (class "Default")
      (node (ref "PROZ1") (pin "2") (pinfunction "VDDA_IN_2") (pintype "passive"))
    )
    (net (code "142") (name "unconnected-(PROZ1F-VDDA_OUT-Pad4)") (class "Default")
      (node (ref "PROZ1") (pin "4") (pinfunction "VDDA_OUT_4") (pintype "passive"))
    )
    (net (code "143") (name "unconnected-(S_CAN1-PadP$3)") (class "Default")
      (node (ref "S_CAN1") (pin "P$3") (pinfunction "P$3_P$3") (pintype "bidirectional"))
    )
    (net (code "144") (name "unconnected-(S_CAN1_ROFF-PadP$3)") (class "Default")
      (node (ref "S_CAN1_ROFF") (pin "P$3") (pinfunction "P$3_P$3") (pintype "bidirectional"))
    )
    (net (code "145") (name "unconnected-(S_CAN2_ROFF-PadP$3)") (class "Default")
      (node (ref "S_CAN2_ROFF") (pin "P$3") (pinfunction "P$3_P$3") (pintype "bidirectional"))
    )
  )
)
